# EMG_V02.net
KiCad netlist of a schematic drawn in Altium Designer
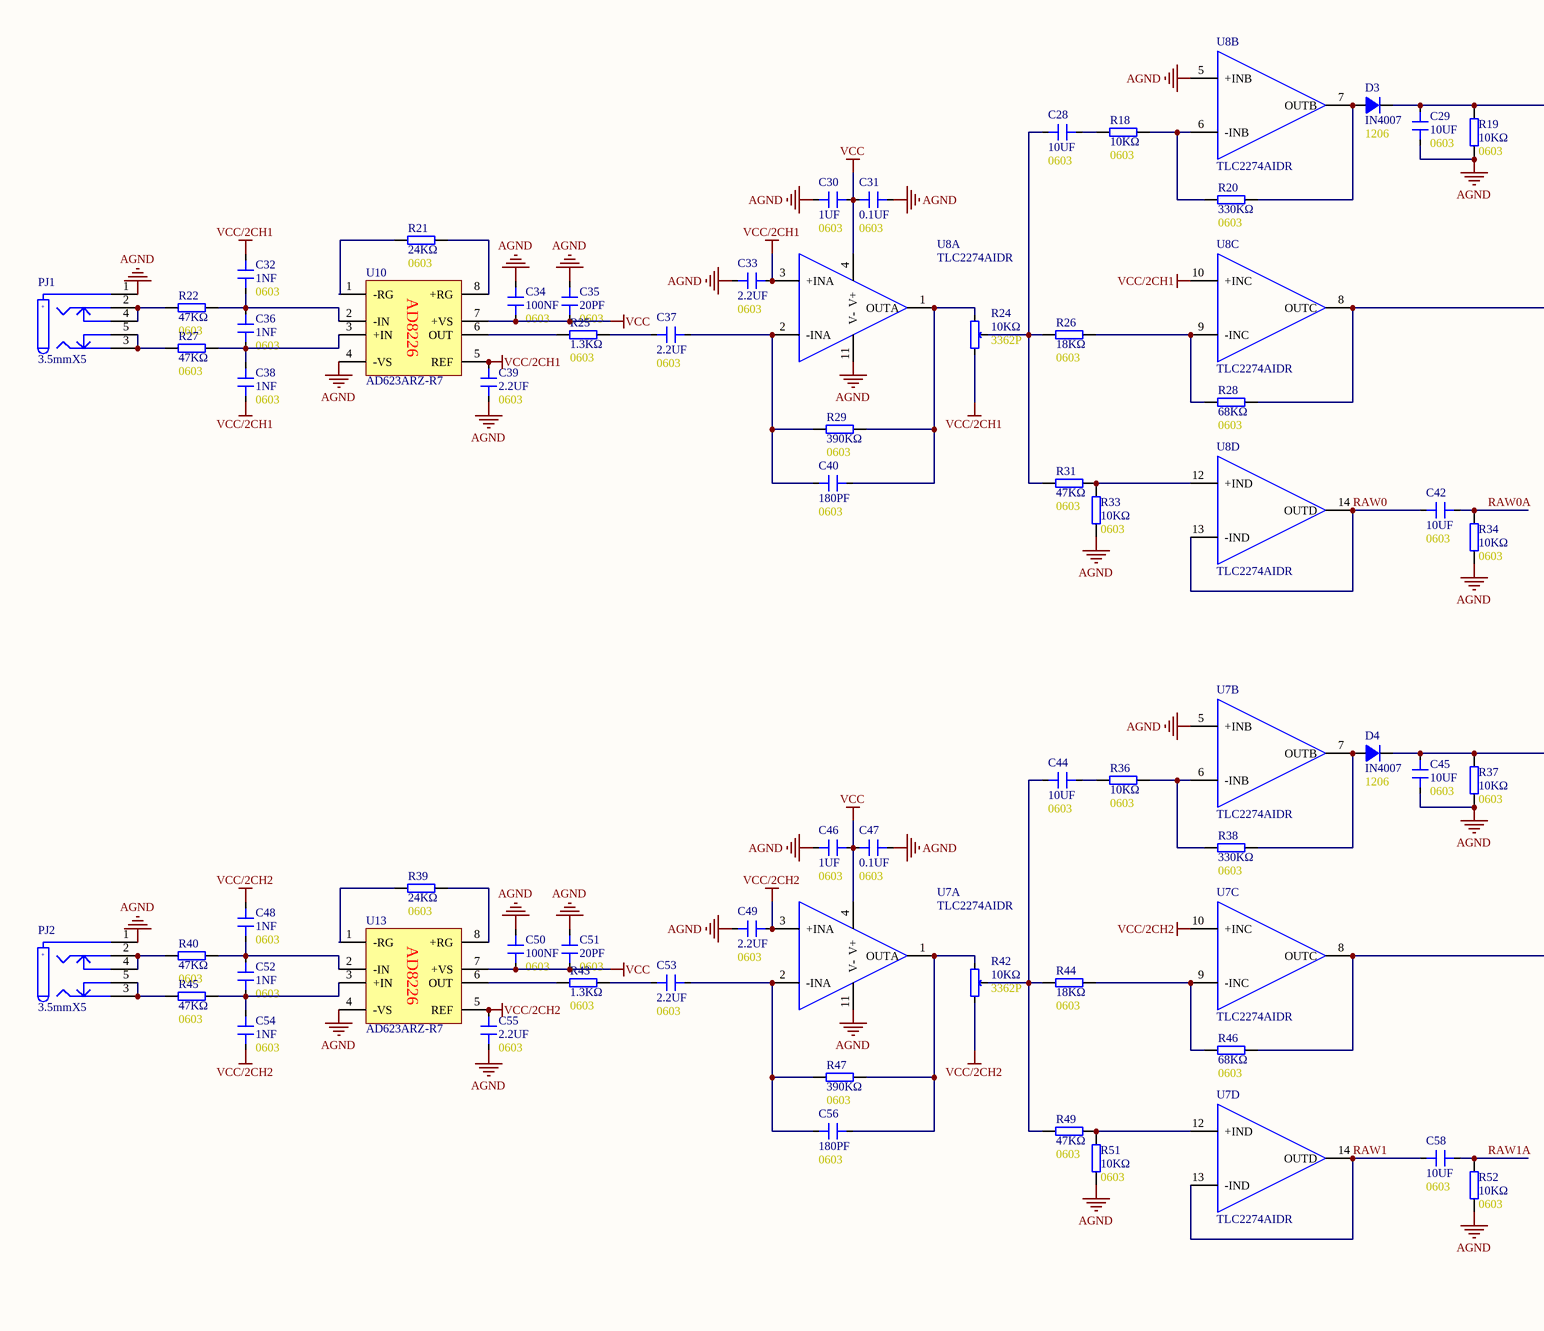
[diagram p0: EMG_V02.SchDoc, top left]
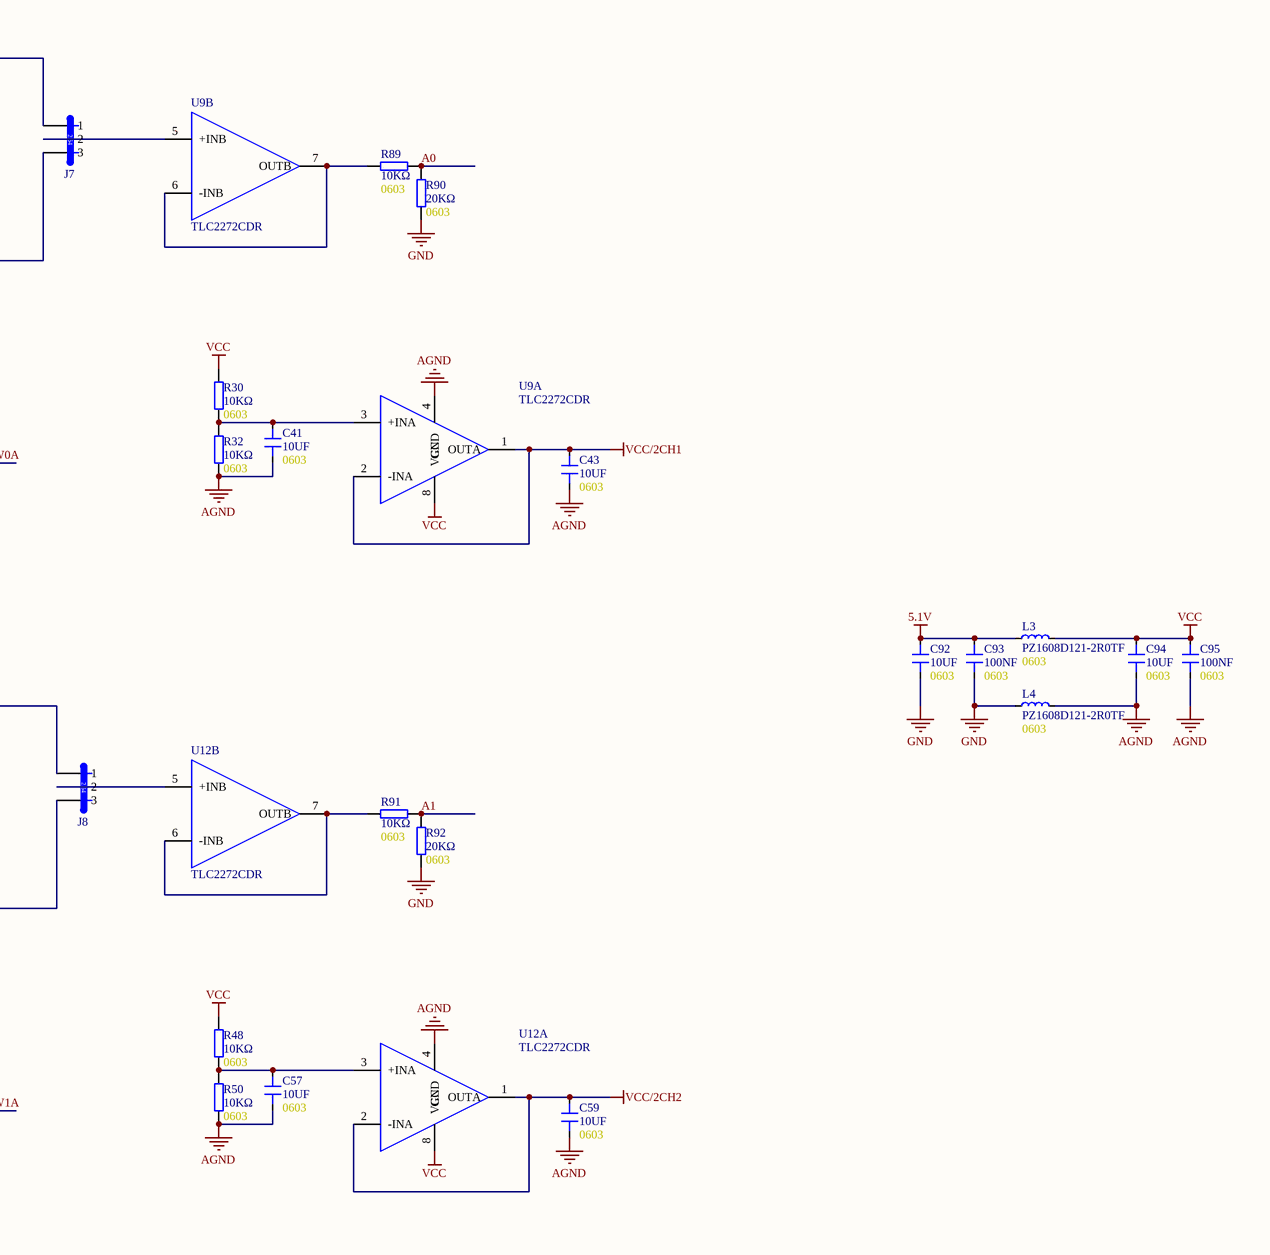
[diagram p1: EMG_V02.SchDoc, top right]
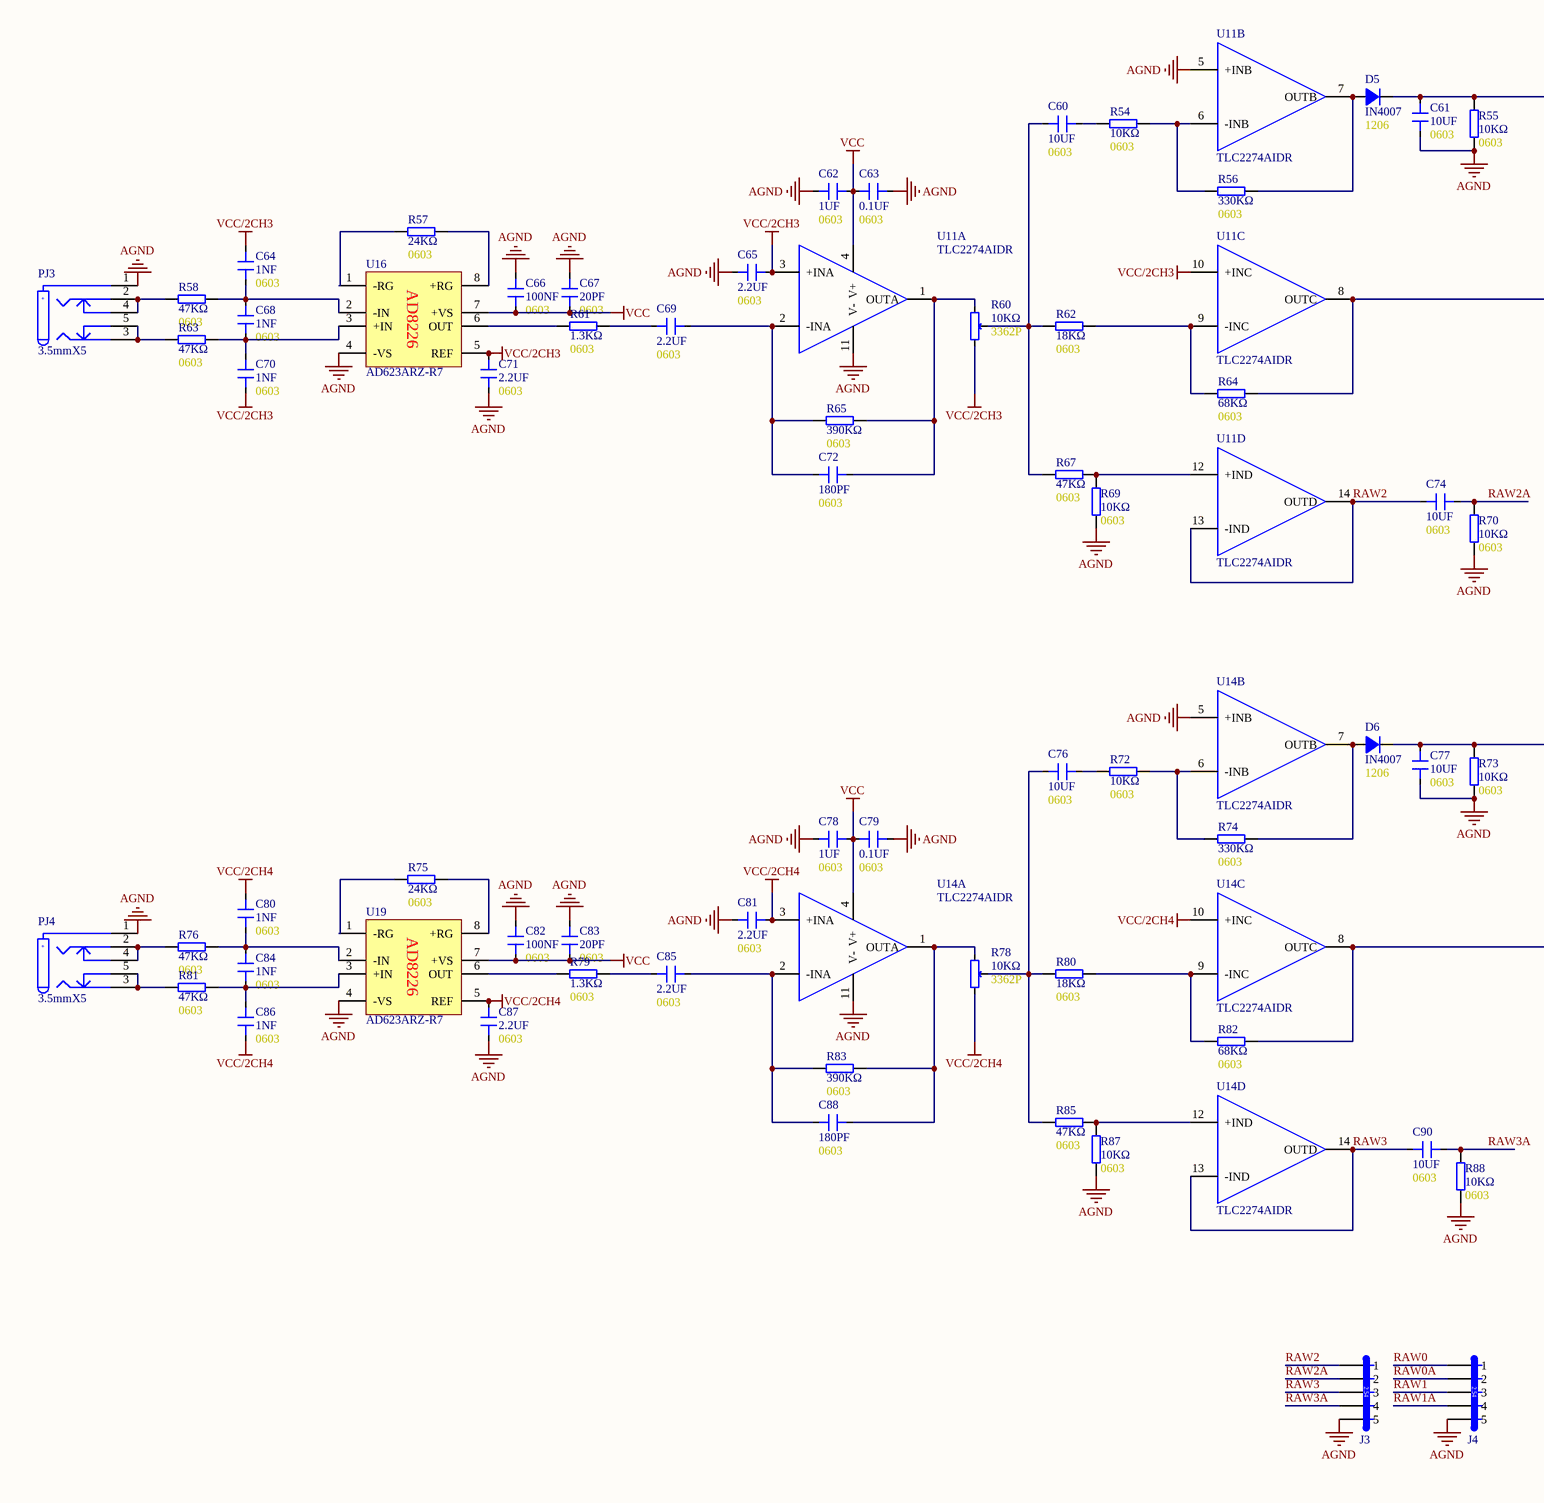
[diagram p2: EMG_V02.SchDoc, bottom left]
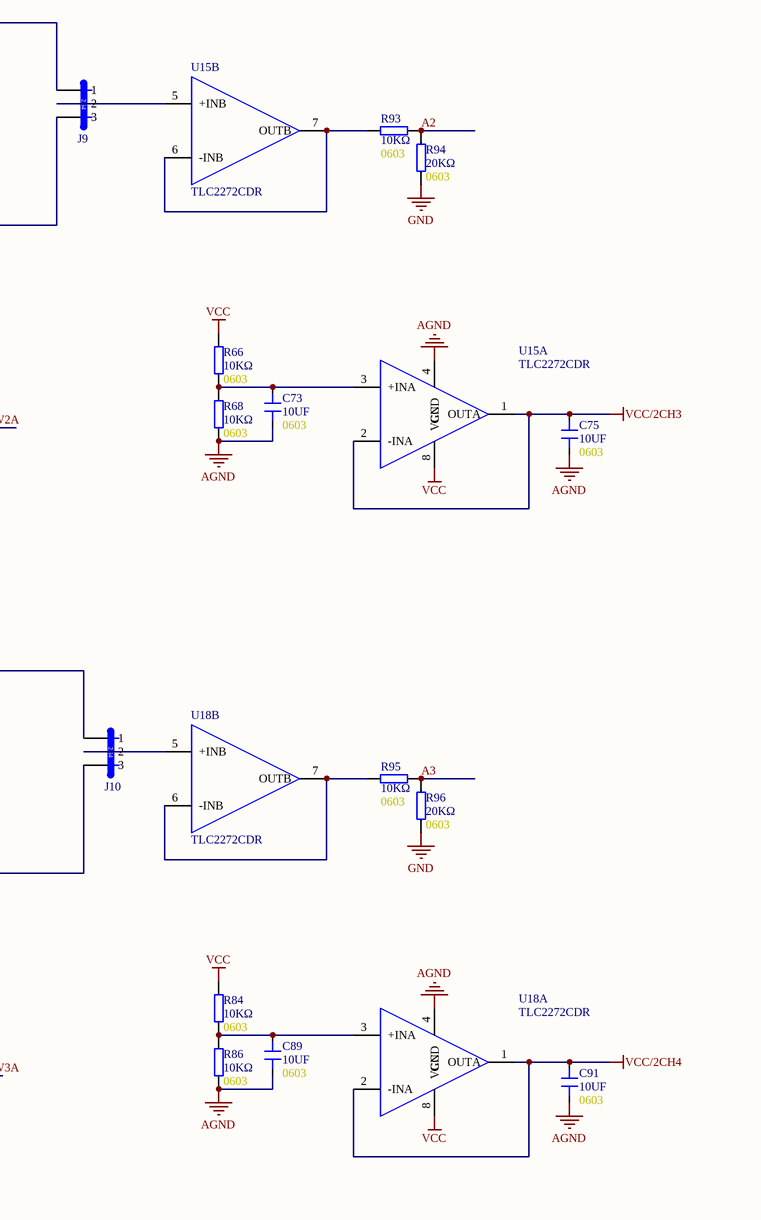
[diagram p3: EMG_V02.SchDoc, bottom right]

(export (version "E")
  (design (tool "Eeschema 10.0.6"))
  (components
    (comp (ref "C28")
      (value "10UF")
      (footprint "CAP - 0603")
      (description "贴片电容，0603封装")
      (fields (field (name "封装类型") "0603"))
      (libsource (lib "冯奇 - 标准集成库") (part "CAP - 0603"))
    )
    (comp (ref "C29")
      (value "10UF")
      (footprint "CAP - 0603")
      (description "贴片电容，0603封装")
      (fields (field (name "封装类型") "0603"))
      (libsource (lib "冯奇 - 标准集成库") (part "CAP - 0603"))
    )
    (comp (ref "C30")
      (value "1UF")
      (footprint "CAP - 0603")
      (description "贴片电容，0603封装")
      (fields (field (name "封装类型") "0603"))
      (libsource (lib "冯奇 - 标准集成库") (part "CAP - 0603"))
    )
    (comp (ref "C31")
      (value "0.1UF")
      (footprint "CAP - 0603")
      (description "贴片电容，0603封装")
      (fields (field (name "封装类型") "0603"))
      (libsource (lib "冯奇 - 标准集成库") (part "CAP - 0603"))
    )
    (comp (ref "C32")
      (value "1NF")
      (footprint "CAP - 0603")
      (description "贴片电容，0603封装")
      (fields (field (name "封装类型") "0603"))
      (libsource (lib "冯奇 - 标准集成库") (part "CAP - 0603"))
    )
    (comp (ref "C33")
      (value "2.2UF")
      (footprint "CAP - 0603")
      (description "贴片电容，0603封装")
      (fields (field (name "封装类型") "0603"))
      (libsource (lib "冯奇 - 标准集成库") (part "CAP - 0603"))
    )
    (comp (ref "C34")
      (value "100NF")
      (footprint "CAP - 0603")
      (description "贴片电容，0603封装")
      (fields (field (name "封装类型") "0603"))
      (libsource (lib "冯奇 - 标准集成库") (part "CAP - 0603"))
    )
    (comp (ref "C35")
      (value "20PF")
      (footprint "CAP - 0603")
      (description "贴片电容，0603封装")
      (fields (field (name "封装类型") "0603"))
      (libsource (lib "冯奇 - 标准集成库") (part "CAP - 0603"))
    )
    (comp (ref "C36")
      (value "1NF")
      (footprint "CAP - 0603")
      (description "贴片电容，0603封装")
      (fields (field (name "封装类型") "0603"))
      (libsource (lib "冯奇 - 标准集成库") (part "CAP - 0603"))
    )
    (comp (ref "C37")
      (value "2.2UF")
      (footprint "CAP - 0603")
      (description "贴片电容，0603封装")
      (fields (field (name "封装类型") "0603"))
      (libsource (lib "冯奇 - 标准集成库") (part "CAP - 0603"))
    )
    (comp (ref "C38")
      (value "1NF")
      (footprint "CAP - 0603")
      (description "贴片电容，0603封装")
      (fields (field (name "封装类型") "0603"))
      (libsource (lib "冯奇 - 标准集成库") (part "CAP - 0603"))
    )
    (comp (ref "C39")
      (value "2.2UF")
      (footprint "CAP - 0603")
      (description "贴片电容，0603封装")
      (fields (field (name "封装类型") "0603"))
      (libsource (lib "冯奇 - 标准集成库") (part "CAP - 0603"))
    )
    (comp (ref "C40")
      (value "180PF")
      (footprint "CAP - 0603")
      (description "贴片电容，0603封装")
      (fields (field (name "封装类型") "0603"))
      (libsource (lib "冯奇 - 标准集成库") (part "CAP - 0603"))
    )
    (comp (ref "C41")
      (value "10UF")
      (footprint "CAP - 0603")
      (description "贴片电容，0603封装")
      (fields (field (name "封装类型") "0603"))
      (libsource (lib "冯奇 - 标准集成库") (part "CAP - 0603"))
    )
    (comp (ref "C42")
      (value "10UF")
      (footprint "CAP - 0603")
      (description "贴片电容，0603封装")
      (fields (field (name "封装类型") "0603"))
      (libsource (lib "冯奇 - 标准集成库") (part "CAP - 0603"))
    )
    (comp (ref "C43")
      (value "10UF")
      (footprint "CAP - 0603")
      (description "贴片电容，0603封装")
      (fields (field (name "封装类型") "0603"))
      (libsource (lib "冯奇 - 标准集成库") (part "CAP - 0603"))
    )
    (comp (ref "C44")
      (value "10UF")
      (footprint "CAP - 0603")
      (description "贴片电容，0603封装")
      (fields (field (name "封装类型") "0603"))
      (libsource (lib "冯奇 - 标准集成库") (part "CAP - 0603"))
    )
    (comp (ref "C45")
      (value "10UF")
      (footprint "CAP - 0603")
      (description "贴片电容，0603封装")
      (fields (field (name "封装类型") "0603"))
      (libsource (lib "冯奇 - 标准集成库") (part "CAP - 0603"))
    )
    (comp (ref "C46")
      (value "1UF")
      (footprint "CAP - 0603")
      (description "贴片电容，0603封装")
      (fields (field (name "封装类型") "0603"))
      (libsource (lib "冯奇 - 标准集成库") (part "CAP - 0603"))
    )
    (comp (ref "C47")
      (value "0.1UF")
      (footprint "CAP - 0603")
      (description "贴片电容，0603封装")
      (fields (field (name "封装类型") "0603"))
      (libsource (lib "冯奇 - 标准集成库") (part "CAP - 0603"))
    )
    (comp (ref "C48")
      (value "1NF")
      (footprint "CAP - 0603")
      (description "贴片电容，0603封装")
      (fields (field (name "封装类型") "0603"))
      (libsource (lib "冯奇 - 标准集成库") (part "CAP - 0603"))
    )
    (comp (ref "C49")
      (value "2.2UF")
      (footprint "CAP - 0603")
      (description "贴片电容，0603封装")
      (fields (field (name "封装类型") "0603"))
      (libsource (lib "冯奇 - 标准集成库") (part "CAP - 0603"))
    )
    (comp (ref "C50")
      (value "100NF")
      (footprint "CAP - 0603")
      (description "贴片电容，0603封装")
      (fields (field (name "封装类型") "0603"))
      (libsource (lib "冯奇 - 标准集成库") (part "CAP - 0603"))
    )
    (comp (ref "C51")
      (value "20PF")
      (footprint "CAP - 0603")
      (description "贴片电容，0603封装")
      (fields (field (name "封装类型") "0603"))
      (libsource (lib "冯奇 - 标准集成库") (part "CAP - 0603"))
    )
    (comp (ref "C52")
      (value "1NF")
      (footprint "CAP - 0603")
      (description "贴片电容，0603封装")
      (fields (field (name "封装类型") "0603"))
      (libsource (lib "冯奇 - 标准集成库") (part "CAP - 0603"))
    )
    (comp (ref "C53")
      (value "2.2UF")
      (footprint "CAP - 0603")
      (description "贴片电容，0603封装")
      (fields (field (name "封装类型") "0603"))
      (libsource (lib "冯奇 - 标准集成库") (part "CAP - 0603"))
    )
    (comp (ref "C54")
      (value "1NF")
      (footprint "CAP - 0603")
      (description "贴片电容，0603封装")
      (fields (field (name "封装类型") "0603"))
      (libsource (lib "冯奇 - 标准集成库") (part "CAP - 0603"))
    )
    (comp (ref "C55")
      (value "2.2UF")
      (footprint "CAP - 0603")
      (description "贴片电容，0603封装")
      (fields (field (name "封装类型") "0603"))
      (libsource (lib "冯奇 - 标准集成库") (part "CAP - 0603"))
    )
    (comp (ref "C56")
      (value "180PF")
      (footprint "CAP - 0603")
      (description "贴片电容，0603封装")
      (fields (field (name "封装类型") "0603"))
      (libsource (lib "冯奇 - 标准集成库") (part "CAP - 0603"))
    )
    (comp (ref "C57")
      (value "10UF")
      (footprint "CAP - 0603")
      (description "贴片电容，0603封装")
      (fields (field (name "封装类型") "0603"))
      (libsource (lib "冯奇 - 标准集成库") (part "CAP - 0603"))
    )
    (comp (ref "C58")
      (value "10UF")
      (footprint "CAP - 0603")
      (description "贴片电容，0603封装")
      (fields (field (name "封装类型") "0603"))
      (libsource (lib "冯奇 - 标准集成库") (part "CAP - 0603"))
    )
    (comp (ref "C59")
      (value "10UF")
      (footprint "CAP - 0603")
      (description "贴片电容，0603封装")
      (fields (field (name "封装类型") "0603"))
      (libsource (lib "冯奇 - 标准集成库") (part "CAP - 0603"))
    )
    (comp (ref "C60")
      (value "10UF")
      (footprint "CAP - 0603")
      (description "贴片电容，0603封装")
      (fields (field (name "封装类型") "0603"))
      (libsource (lib "冯奇 - 标准集成库") (part "CAP - 0603"))
    )
    (comp (ref "C61")
      (value "10UF")
      (footprint "CAP - 0603")
      (description "贴片电容，0603封装")
      (fields (field (name "封装类型") "0603"))
      (libsource (lib "冯奇 - 标准集成库") (part "CAP - 0603"))
    )
    (comp (ref "C62")
      (value "1UF")
      (footprint "CAP - 0603")
      (description "贴片电容，0603封装")
      (fields (field (name "封装类型") "0603"))
      (libsource (lib "冯奇 - 标准集成库") (part "CAP - 0603"))
    )
    (comp (ref "C63")
      (value "0.1UF")
      (footprint "CAP - 0603")
      (description "贴片电容，0603封装")
      (fields (field (name "封装类型") "0603"))
      (libsource (lib "冯奇 - 标准集成库") (part "CAP - 0603"))
    )
    (comp (ref "C64")
      (value "1NF")
      (footprint "CAP - 0603")
      (description "贴片电容，0603封装")
      (fields (field (name "封装类型") "0603"))
      (libsource (lib "冯奇 - 标准集成库") (part "CAP - 0603"))
    )
    (comp (ref "C65")
      (value "2.2UF")
      (footprint "CAP - 0603")
      (description "贴片电容，0603封装")
      (fields (field (name "封装类型") "0603"))
      (libsource (lib "冯奇 - 标准集成库") (part "CAP - 0603"))
    )
    (comp (ref "C66")
      (value "100NF")
      (footprint "CAP - 0603")
      (description "贴片电容，0603封装")
      (fields (field (name "封装类型") "0603"))
      (libsource (lib "冯奇 - 标准集成库") (part "CAP - 0603"))
    )
    (comp (ref "C67")
      (value "20PF")
      (footprint "CAP - 0603")
      (description "贴片电容，0603封装")
      (fields (field (name "封装类型") "0603"))
      (libsource (lib "冯奇 - 标准集成库") (part "CAP - 0603"))
    )
    (comp (ref "C68")
      (value "1NF")
      (footprint "CAP - 0603")
      (description "贴片电容，0603封装")
      (fields (field (name "封装类型") "0603"))
      (libsource (lib "冯奇 - 标准集成库") (part "CAP - 0603"))
    )
    (comp (ref "C69")
      (value "2.2UF")
      (footprint "CAP - 0603")
      (description "贴片电容，0603封装")
      (fields (field (name "封装类型") "0603"))
      (libsource (lib "冯奇 - 标准集成库") (part "CAP - 0603"))
    )
    (comp (ref "C70")
      (value "1NF")
      (footprint "CAP - 0603")
      (description "贴片电容，0603封装")
      (fields (field (name "封装类型") "0603"))
      (libsource (lib "冯奇 - 标准集成库") (part "CAP - 0603"))
    )
    (comp (ref "C71")
      (value "2.2UF")
      (footprint "CAP - 0603")
      (description "贴片电容，0603封装")
      (fields (field (name "封装类型") "0603"))
      (libsource (lib "冯奇 - 标准集成库") (part "CAP - 0603"))
    )
    (comp (ref "C72")
      (value "180PF")
      (footprint "CAP - 0603")
      (description "贴片电容，0603封装")
      (fields (field (name "封装类型") "0603"))
      (libsource (lib "冯奇 - 标准集成库") (part "CAP - 0603"))
    )
    (comp (ref "C73")
      (value "10UF")
      (footprint "CAP - 0603")
      (description "贴片电容，0603封装")
      (fields (field (name "封装类型") "0603"))
      (libsource (lib "冯奇 - 标准集成库") (part "CAP - 0603"))
    )
    (comp (ref "C74")
      (value "10UF")
      (footprint "CAP - 0603")
      (description "贴片电容，0603封装")
      (fields (field (name "封装类型") "0603"))
      (libsource (lib "冯奇 - 标准集成库") (part "CAP - 0603"))
    )
    (comp (ref "C75")
      (value "10UF")
      (footprint "CAP - 0603")
      (description "贴片电容，0603封装")
      (fields (field (name "封装类型") "0603"))
      (libsource (lib "冯奇 - 标准集成库") (part "CAP - 0603"))
    )
    (comp (ref "C76")
      (value "10UF")
      (footprint "CAP - 0603")
      (description "贴片电容，0603封装")
      (fields (field (name "封装类型") "0603"))
      (libsource (lib "冯奇 - 标准集成库") (part "CAP - 0603"))
    )
    (comp (ref "C77")
      (value "10UF")
      (footprint "CAP - 0603")
      (description "贴片电容，0603封装")
      (fields (field (name "封装类型") "0603"))
      (libsource (lib "冯奇 - 标准集成库") (part "CAP - 0603"))
    )
    (comp (ref "C78")
      (value "1UF")
      (footprint "CAP - 0603")
      (description "贴片电容，0603封装")
      (fields (field (name "封装类型") "0603"))
      (libsource (lib "冯奇 - 标准集成库") (part "CAP - 0603"))
    )
    (comp (ref "C79")
      (value "0.1UF")
      (footprint "CAP - 0603")
      (description "贴片电容，0603封装")
      (fields (field (name "封装类型") "0603"))
      (libsource (lib "冯奇 - 标准集成库") (part "CAP - 0603"))
    )
    (comp (ref "C80")
      (value "1NF")
      (footprint "CAP - 0603")
      (description "贴片电容，0603封装")
      (fields (field (name "封装类型") "0603"))
      (libsource (lib "冯奇 - 标准集成库") (part "CAP - 0603"))
    )
    (comp (ref "C81")
      (value "2.2UF")
      (footprint "CAP - 0603")
      (description "贴片电容，0603封装")
      (fields (field (name "封装类型") "0603"))
      (libsource (lib "冯奇 - 标准集成库") (part "CAP - 0603"))
    )
    (comp (ref "C82")
      (value "100NF")
      (footprint "CAP - 0603")
      (description "贴片电容，0603封装")
      (fields (field (name "封装类型") "0603"))
      (libsource (lib "冯奇 - 标准集成库") (part "CAP - 0603"))
    )
    (comp (ref "C83")
      (value "20PF")
      (footprint "CAP - 0603")
      (description "贴片电容，0603封装")
      (fields (field (name "封装类型") "0603"))
      (libsource (lib "冯奇 - 标准集成库") (part "CAP - 0603"))
    )
    (comp (ref "C84")
      (value "1NF")
      (footprint "CAP - 0603")
      (description "贴片电容，0603封装")
      (fields (field (name "封装类型") "0603"))
      (libsource (lib "冯奇 - 标准集成库") (part "CAP - 0603"))
    )
    (comp (ref "C85")
      (value "2.2UF")
      (footprint "CAP - 0603")
      (description "贴片电容，0603封装")
      (fields (field (name "封装类型") "0603"))
      (libsource (lib "冯奇 - 标准集成库") (part "CAP - 0603"))
    )
    (comp (ref "C86")
      (value "1NF")
      (footprint "CAP - 0603")
      (description "贴片电容，0603封装")
      (fields (field (name "封装类型") "0603"))
      (libsource (lib "冯奇 - 标准集成库") (part "CAP - 0603"))
    )
    (comp (ref "C87")
      (value "2.2UF")
      (footprint "CAP - 0603")
      (description "贴片电容，0603封装")
      (fields (field (name "封装类型") "0603"))
      (libsource (lib "冯奇 - 标准集成库") (part "CAP - 0603"))
    )
    (comp (ref "C88")
      (value "180PF")
      (footprint "CAP - 0603")
      (description "贴片电容，0603封装")
      (fields (field (name "封装类型") "0603"))
      (libsource (lib "冯奇 - 标准集成库") (part "CAP - 0603"))
    )
    (comp (ref "C89")
      (value "10UF")
      (footprint "CAP - 0603")
      (description "贴片电容，0603封装")
      (fields (field (name "封装类型") "0603"))
      (libsource (lib "冯奇 - 标准集成库") (part "CAP - 0603"))
    )
    (comp (ref "C90")
      (value "10UF")
      (footprint "CAP - 0603")
      (description "贴片电容，0603封装")
      (fields (field (name "封装类型") "0603"))
      (libsource (lib "冯奇 - 标准集成库") (part "CAP - 0603"))
    )
    (comp (ref "C91")
      (value "10UF")
      (footprint "CAP - 0603")
      (description "贴片电容，0603封装")
      (fields (field (name "封装类型") "0603"))
      (libsource (lib "冯奇 - 标准集成库") (part "CAP - 0603"))
    )
    (comp (ref "C92")
      (value "10UF")
      (footprint "CAP - 0603")
      (description "贴片电容，0603封装")
      (fields (field (name "封装类型") "0603"))
      (libsource (lib "冯奇 - 标准集成库") (part "CAP - 0603"))
    )
    (comp (ref "C93")
      (value "100NF")
      (footprint "CAP - 0603")
      (description "贴片电容，0603封装")
      (fields (field (name "封装类型") "0603"))
      (libsource (lib "冯奇 - 标准集成库") (part "CAP - 0603"))
    )
    (comp (ref "C94")
      (value "10UF")
      (footprint "CAP - 0603")
      (description "贴片电容，0603封装")
      (fields (field (name "封装类型") "0603"))
      (libsource (lib "冯奇 - 标准集成库") (part "CAP - 0603"))
    )
    (comp (ref "C95")
      (value "100NF")
      (footprint "CAP - 0603")
      (description "贴片电容，0603封装")
      (fields (field (name "封装类型") "0603"))
      (libsource (lib "冯奇 - 标准集成库") (part "CAP - 0603"))
    )
    (comp (ref "D3")
      (value "IN4007")
      (footprint "DIO-1206/SOD123")
      (description "二极管，SOD123/1206封装")
      (fields (field (name "封装类型") "1206"))
      (libsource (lib "冯奇 - 标准集成库") (part "DIO/1206"))
    )
    (comp (ref "D4")
      (value "IN4007")
      (footprint "DIO-1206/SOD123")
      (description "二极管，SOD123/1206封装")
      (fields (field (name "封装类型") "1206"))
      (libsource (lib "冯奇 - 标准集成库") (part "DIO/1206"))
    )
    (comp (ref "D5")
      (value "IN4007")
      (footprint "DIO-1206/SOD123")
      (description "二极管，SOD123/1206封装")
      (fields (field (name "封装类型") "1206"))
      (libsource (lib "冯奇 - 标准集成库") (part "DIO/1206"))
    )
    (comp (ref "D6")
      (value "IN4007")
      (footprint "DIO-1206/SOD123")
      (description "二极管，SOD123/1206封装")
      (fields (field (name "封装类型") "1206"))
      (libsource (lib "冯奇 - 标准集成库") (part "DIO/1206"))
    )
    (comp (ref "J3")
      (value "2.54mm")
      (footprint "PIN/2.54 - 05X01")
      (description "普通插针，间距2.54mm，05X01")
      (libsource (lib "冯奇 - 标准集成库") (part "PIN/2.54 - 05X01"))
    )
    (comp (ref "J4")
      (value "2.54mm")
      (footprint "PIN/2.54 - 05X01")
      (description "普通插针，间距2.54mm，05X01")
      (libsource (lib "冯奇 - 标准集成库") (part "PIN/2.54 - 05X01"))
    )
    (comp (ref "J7")
      (value "2.54mm")
      (footprint "PIN/2.54 - 03X01")
      (description "普通插针，间距2.54mm，03X01")
      (libsource (lib "冯奇 - 标准集成库") (part "PIN/2.54 - 03X01"))
    )
    (comp (ref "J8")
      (value "2.54mm")
      (footprint "PIN/2.54 - 03X01")
      (description "普通插针，间距2.54mm，03X01")
      (libsource (lib "冯奇 - 标准集成库") (part "PIN/2.54 - 03X01"))
    )
    (comp (ref "J9")
      (value "2.54mm")
      (footprint "PIN/2.54 - 03X01")
      (description "普通插针，间距2.54mm，03X01")
      (libsource (lib "冯奇 - 标准集成库") (part "PIN/2.54 - 03X01"))
    )
    (comp (ref "J10")
      (value "2.54mm")
      (footprint "PIN/2.54 - 03X01")
      (description "普通插针，间距2.54mm，03X01")
      (libsource (lib "冯奇 - 标准集成库") (part "PIN/2.54 - 03X01"))
    )
    (comp (ref "L3")
      (value "PZ1608D121-2R0TF")
      (footprint "IND/SMD-0603")
      (description "贴片电感，0603封装")
      (fields (field (name "封装类型") "0603"))
      (libsource (lib "冯奇 - 标准集成库") (part "IND/SMD-0603"))
    )
    (comp (ref "L4")
      (value "PZ1608D121-2R0TF")
      (footprint "IND/SMD-0603")
      (description "贴片电感，0603封装")
      (fields (field (name "封装类型") "0603"))
      (libsource (lib "冯奇 - 标准集成库") (part "IND/SMD-0603"))
    )
    (comp (ref "PJ1")
      (value "PJ-3.5")
      (footprint "PJ/3.5MM")
      (description "耳机插座，3.5MM，直插5脚")
      (fields (field (name "封装类型") "3.5mmX5"))
      (libsource (lib "冯奇 - 标准集成库") (part "PJ/3.5MM"))
    )
    (comp (ref "PJ2")
      (value "PJ-3.5")
      (footprint "PJ/3.5MM")
      (description "耳机插座，3.5MM，直插5脚")
      (fields (field (name "封装类型") "3.5mmX5"))
      (libsource (lib "冯奇 - 标准集成库") (part "PJ/3.5MM"))
    )
    (comp (ref "PJ3")
      (value "PJ-3.5")
      (footprint "PJ/3.5MM")
      (description "耳机插座，3.5MM，直插5脚")
      (fields (field (name "封装类型") "3.5mmX5"))
      (libsource (lib "冯奇 - 标准集成库") (part "PJ/3.5MM"))
    )
    (comp (ref "PJ4")
      (value "PJ-3.5")
      (footprint "PJ/3.5MM")
      (description "耳机插座，3.5MM，直插5脚")
      (fields (field (name "封装类型") "3.5mmX5"))
      (libsource (lib "冯奇 - 标准集成库") (part "PJ/3.5MM"))
    )
    (comp (ref "R18")
      (value "10KΩ")
      (footprint "RES/SMD-0603")
      (description "1/10W，50V，贴片电阻，0603封装")
      (fields (field (name "封装类型") "0603"))
      (libsource (lib "冯奇 - 标准集成库") (part "RES/SMD-0603"))
    )
    (comp (ref "R19")
      (value "10KΩ")
      (footprint "RES/SMD-0603")
      (description "1/10W，50V，贴片电阻，0603封装")
      (fields (field (name "封装类型") "0603"))
      (libsource (lib "") (part "RES/SMD-0603_2"))
    )
    (comp (ref "R20")
      (value "330KΩ")
      (footprint "RES/SMD-0603")
      (description "1/10W，50V，贴片电阻，0603封装")
      (fields (field (name "封装类型") "0603"))
      (libsource (lib "冯奇 - 标准集成库") (part "RES/SMD-0603"))
    )
    (comp (ref "R21")
      (value "24KΩ")
      (footprint "RES/SMD-0603")
      (description "1/10W，50V，贴片电阻，0603封装")
      (fields (field (name "封装类型") "0603"))
      (libsource (lib "冯奇 - 标准集成库") (part "RES/SMD-0603"))
    )
    (comp (ref "R22")
      (value "47KΩ")
      (footprint "RES/SMD-0603")
      (description "1/10W，50V，贴片电阻，0603封装")
      (fields (field (name "封装类型") "0603"))
      (libsource (lib "冯奇 - 标准集成库") (part "RES/SMD-0603"))
    )
    (comp (ref "R24")
      (value "10KΩ")
      (footprint "RES/VARI - 3362P")
      (description "可变电阻，3362P型号")
      (fields (field (name "封装类型") "3362P"))
      (libsource (lib "冯奇 - 标准集成库") (part "RES/VARI-3362P"))
    )
    (comp (ref "R25")
      (value "1.3KΩ")
      (footprint "RES/SMD-0603")
      (description "1/10W，50V，贴片电阻，0603封装")
      (fields (field (name "封装类型") "0603"))
      (libsource (lib "冯奇 - 标准集成库") (part "RES/SMD-0603"))
    )
    (comp (ref "R26")
      (value "18KΩ")
      (footprint "RES/SMD-0603")
      (description "1/10W，50V，贴片电阻，0603封装")
      (fields (field (name "封装类型") "0603"))
      (libsource (lib "冯奇 - 标准集成库") (part "RES/SMD-0603"))
    )
    (comp (ref "R27")
      (value "47KΩ")
      (footprint "RES/SMD-0603")
      (description "1/10W，50V，贴片电阻，0603封装")
      (fields (field (name "封装类型") "0603"))
      (libsource (lib "冯奇 - 标准集成库") (part "RES/SMD-0603"))
    )
    (comp (ref "R28")
      (value "68KΩ")
      (footprint "RES/SMD-0603")
      (description "1/10W，50V，贴片电阻，0603封装")
      (fields (field (name "封装类型") "0603"))
      (libsource (lib "冯奇 - 标准集成库") (part "RES/SMD-0603"))
    )
    (comp (ref "R29")
      (value "390KΩ")
      (footprint "RES/SMD-0603")
      (description "1/10W，50V，贴片电阻，0603封装")
      (fields (field (name "封装类型") "0603"))
      (libsource (lib "冯奇 - 标准集成库") (part "RES/SMD-0603"))
    )
    (comp (ref "R30")
      (value "10KΩ")
      (footprint "RES/SMD-0603")
      (description "1/10W，50V，贴片电阻，0603封装")
      (fields (field (name "封装类型") "0603"))
      (libsource (lib "") (part "RES/SMD-0603_1"))
    )
    (comp (ref "R31")
      (value "47KΩ")
      (footprint "RES/SMD-0603")
      (description "1/10W，50V，贴片电阻，0603封装")
      (fields (field (name "封装类型") "0603"))
      (libsource (lib "冯奇 - 标准集成库") (part "RES/SMD-0603"))
    )
    (comp (ref "R32")
      (value "10KΩ")
      (footprint "RES/SMD-0603")
      (description "1/10W，50V，贴片电阻，0603封装")
      (fields (field (name "封装类型") "0603"))
      (libsource (lib "") (part "RES/SMD-0603_1"))
    )
    (comp (ref "R33")
      (value "10KΩ")
      (footprint "RES/SMD-0603")
      (description "1/10W，50V，贴片电阻，0603封装")
      (fields (field (name "封装类型") "0603"))
      (libsource (lib "") (part "RES/SMD-0603_2"))
    )
    (comp (ref "R34")
      (value "10KΩ")
      (footprint "RES/SMD-0603")
      (description "1/10W，50V，贴片电阻，0603封装")
      (fields (field (name "封装类型") "0603"))
      (libsource (lib "") (part "RES/SMD-0603_2"))
    )
    (comp (ref "R36")
      (value "10KΩ")
      (footprint "RES/SMD-0603")
      (description "1/10W，50V，贴片电阻，0603封装")
      (fields (field (name "封装类型") "0603"))
      (libsource (lib "冯奇 - 标准集成库") (part "RES/SMD-0603"))
    )
    (comp (ref "R37")
      (value "10KΩ")
      (footprint "RES/SMD-0603")
      (description "1/10W，50V，贴片电阻，0603封装")
      (fields (field (name "封装类型") "0603"))
      (libsource (lib "") (part "RES/SMD-0603_2"))
    )
    (comp (ref "R38")
      (value "330KΩ")
      (footprint "RES/SMD-0603")
      (description "1/10W，50V，贴片电阻，0603封装")
      (fields (field (name "封装类型") "0603"))
      (libsource (lib "冯奇 - 标准集成库") (part "RES/SMD-0603"))
    )
    (comp (ref "R39")
      (value "24KΩ")
      (footprint "RES/SMD-0603")
      (description "1/10W，50V，贴片电阻，0603封装")
      (fields (field (name "封装类型") "0603"))
      (libsource (lib "冯奇 - 标准集成库") (part "RES/SMD-0603"))
    )
    (comp (ref "R40")
      (value "47KΩ")
      (footprint "RES/SMD-0603")
      (description "1/10W，50V，贴片电阻，0603封装")
      (fields (field (name "封装类型") "0603"))
      (libsource (lib "冯奇 - 标准集成库") (part "RES/SMD-0603"))
    )
    (comp (ref "R42")
      (value "10KΩ")
      (footprint "RES/VARI - 3362P")
      (description "可变电阻，3362P型号")
      (fields (field (name "封装类型") "3362P"))
      (libsource (lib "冯奇 - 标准集成库") (part "RES/VARI-3362P"))
    )
    (comp (ref "R43")
      (value "1.3KΩ")
      (footprint "RES/SMD-0603")
      (description "1/10W，50V，贴片电阻，0603封装")
      (fields (field (name "封装类型") "0603"))
      (libsource (lib "冯奇 - 标准集成库") (part "RES/SMD-0603"))
    )
    (comp (ref "R44")
      (value "18KΩ")
      (footprint "RES/SMD-0603")
      (description "1/10W，50V，贴片电阻，0603封装")
      (fields (field (name "封装类型") "0603"))
      (libsource (lib "冯奇 - 标准集成库") (part "RES/SMD-0603"))
    )
    (comp (ref "R45")
      (value "47KΩ")
      (footprint "RES/SMD-0603")
      (description "1/10W，50V，贴片电阻，0603封装")
      (fields (field (name "封装类型") "0603"))
      (libsource (lib "冯奇 - 标准集成库") (part "RES/SMD-0603"))
    )
    (comp (ref "R46")
      (value "68KΩ")
      (footprint "RES/SMD-0603")
      (description "1/10W，50V，贴片电阻，0603封装")
      (fields (field (name "封装类型") "0603"))
      (libsource (lib "冯奇 - 标准集成库") (part "RES/SMD-0603"))
    )
    (comp (ref "R47")
      (value "390KΩ")
      (footprint "RES/SMD-0603")
      (description "1/10W，50V，贴片电阻，0603封装")
      (fields (field (name "封装类型") "0603"))
      (libsource (lib "冯奇 - 标准集成库") (part "RES/SMD-0603"))
    )
    (comp (ref "R48")
      (value "10KΩ")
      (footprint "RES/SMD-0603")
      (description "1/10W，50V，贴片电阻，0603封装")
      (fields (field (name "封装类型") "0603"))
      (libsource (lib "") (part "RES/SMD-0603_1"))
    )
    (comp (ref "R49")
      (value "47KΩ")
      (footprint "RES/SMD-0603")
      (description "1/10W，50V，贴片电阻，0603封装")
      (fields (field (name "封装类型") "0603"))
      (libsource (lib "冯奇 - 标准集成库") (part "RES/SMD-0603"))
    )
    (comp (ref "R50")
      (value "10KΩ")
      (footprint "RES/SMD-0603")
      (description "1/10W，50V，贴片电阻，0603封装")
      (fields (field (name "封装类型") "0603"))
      (libsource (lib "") (part "RES/SMD-0603_1"))
    )
    (comp (ref "R51")
      (value "10KΩ")
      (footprint "RES/SMD-0603")
      (description "1/10W，50V，贴片电阻，0603封装")
      (fields (field (name "封装类型") "0603"))
      (libsource (lib "") (part "RES/SMD-0603_2"))
    )
    (comp (ref "R52")
      (value "10KΩ")
      (footprint "RES/SMD-0603")
      (description "1/10W，50V，贴片电阻，0603封装")
      (fields (field (name "封装类型") "0603"))
      (libsource (lib "") (part "RES/SMD-0603_2"))
    )
    (comp (ref "R54")
      (value "10KΩ")
      (footprint "RES/SMD-0603")
      (description "1/10W，50V，贴片电阻，0603封装")
      (fields (field (name "封装类型") "0603"))
      (libsource (lib "冯奇 - 标准集成库") (part "RES/SMD-0603"))
    )
    (comp (ref "R55")
      (value "10KΩ")
      (footprint "RES/SMD-0603")
      (description "1/10W，50V，贴片电阻，0603封装")
      (fields (field (name "封装类型") "0603"))
      (libsource (lib "") (part "RES/SMD-0603_2"))
    )
    (comp (ref "R56")
      (value "330KΩ")
      (footprint "RES/SMD-0603")
      (description "1/10W，50V，贴片电阻，0603封装")
      (fields (field (name "封装类型") "0603"))
      (libsource (lib "冯奇 - 标准集成库") (part "RES/SMD-0603"))
    )
    (comp (ref "R57")
      (value "24KΩ")
      (footprint "RES/SMD-0603")
      (description "1/10W，50V，贴片电阻，0603封装")
      (fields (field (name "封装类型") "0603"))
      (libsource (lib "冯奇 - 标准集成库") (part "RES/SMD-0603"))
    )
    (comp (ref "R58")
      (value "47KΩ")
      (footprint "RES/SMD-0603")
      (description "1/10W，50V，贴片电阻，0603封装")
      (fields (field (name "封装类型") "0603"))
      (libsource (lib "冯奇 - 标准集成库") (part "RES/SMD-0603"))
    )
    (comp (ref "R60")
      (value "10KΩ")
      (footprint "RES/VARI - 3362P")
      (description "可变电阻，3362P型号")
      (fields (field (name "封装类型") "3362P"))
      (libsource (lib "冯奇 - 标准集成库") (part "RES/VARI-3362P"))
    )
    (comp (ref "R61")
      (value "1.3KΩ")
      (footprint "RES/SMD-0603")
      (description "1/10W，50V，贴片电阻，0603封装")
      (fields (field (name "封装类型") "0603"))
      (libsource (lib "冯奇 - 标准集成库") (part "RES/SMD-0603"))
    )
    (comp (ref "R62")
      (value "18KΩ")
      (footprint "RES/SMD-0603")
      (description "1/10W，50V，贴片电阻，0603封装")
      (fields (field (name "封装类型") "0603"))
      (libsource (lib "冯奇 - 标准集成库") (part "RES/SMD-0603"))
    )
    (comp (ref "R63")
      (value "47KΩ")
      (footprint "RES/SMD-0603")
      (description "1/10W，50V，贴片电阻，0603封装")
      (fields (field (name "封装类型") "0603"))
      (libsource (lib "冯奇 - 标准集成库") (part "RES/SMD-0603"))
    )
    (comp (ref "R64")
      (value "68KΩ")
      (footprint "RES/SMD-0603")
      (description "1/10W，50V，贴片电阻，0603封装")
      (fields (field (name "封装类型") "0603"))
      (libsource (lib "冯奇 - 标准集成库") (part "RES/SMD-0603"))
    )
    (comp (ref "R65")
      (value "390KΩ")
      (footprint "RES/SMD-0603")
      (description "1/10W，50V，贴片电阻，0603封装")
      (fields (field (name "封装类型") "0603"))
      (libsource (lib "冯奇 - 标准集成库") (part "RES/SMD-0603"))
    )
    (comp (ref "R66")
      (value "10KΩ")
      (footprint "RES/SMD-0603")
      (description "1/10W，50V，贴片电阻，0603封装")
      (fields (field (name "封装类型") "0603"))
      (libsource (lib "") (part "RES/SMD-0603_1"))
    )
    (comp (ref "R67")
      (value "47KΩ")
      (footprint "RES/SMD-0603")
      (description "1/10W，50V，贴片电阻，0603封装")
      (fields (field (name "封装类型") "0603"))
      (libsource (lib "冯奇 - 标准集成库") (part "RES/SMD-0603"))
    )
    (comp (ref "R68")
      (value "10KΩ")
      (footprint "RES/SMD-0603")
      (description "1/10W，50V，贴片电阻，0603封装")
      (fields (field (name "封装类型") "0603"))
      (libsource (lib "") (part "RES/SMD-0603_1"))
    )
    (comp (ref "R69")
      (value "10KΩ")
      (footprint "RES/SMD-0603")
      (description "1/10W，50V，贴片电阻，0603封装")
      (fields (field (name "封装类型") "0603"))
      (libsource (lib "") (part "RES/SMD-0603_2"))
    )
    (comp (ref "R70")
      (value "10KΩ")
      (footprint "RES/SMD-0603")
      (description "1/10W，50V，贴片电阻，0603封装")
      (fields (field (name "封装类型") "0603"))
      (libsource (lib "") (part "RES/SMD-0603_2"))
    )
    (comp (ref "R72")
      (value "10KΩ")
      (footprint "RES/SMD-0603")
      (description "1/10W，50V，贴片电阻，0603封装")
      (fields (field (name "封装类型") "0603"))
      (libsource (lib "冯奇 - 标准集成库") (part "RES/SMD-0603"))
    )
    (comp (ref "R73")
      (value "10KΩ")
      (footprint "RES/SMD-0603")
      (description "1/10W，50V，贴片电阻，0603封装")
      (fields (field (name "封装类型") "0603"))
      (libsource (lib "") (part "RES/SMD-0603_2"))
    )
    (comp (ref "R74")
      (value "330KΩ")
      (footprint "RES/SMD-0603")
      (description "1/10W，50V，贴片电阻，0603封装")
      (fields (field (name "封装类型") "0603"))
      (libsource (lib "冯奇 - 标准集成库") (part "RES/SMD-0603"))
    )
    (comp (ref "R75")
      (value "24KΩ")
      (footprint "RES/SMD-0603")
      (description "1/10W，50V，贴片电阻，0603封装")
      (fields (field (name "封装类型") "0603"))
      (libsource (lib "冯奇 - 标准集成库") (part "RES/SMD-0603"))
    )
    (comp (ref "R76")
      (value "47KΩ")
      (footprint "RES/SMD-0603")
      (description "1/10W，50V，贴片电阻，0603封装")
      (fields (field (name "封装类型") "0603"))
      (libsource (lib "冯奇 - 标准集成库") (part "RES/SMD-0603"))
    )
    (comp (ref "R78")
      (value "10KΩ")
      (footprint "RES/VARI - 3362P")
      (description "可变电阻，3362P型号")
      (fields (field (name "封装类型") "3362P"))
      (libsource (lib "冯奇 - 标准集成库") (part "RES/VARI-3362P"))
    )
    (comp (ref "R79")
      (value "1.3KΩ")
      (footprint "RES/SMD-0603")
      (description "1/10W，50V，贴片电阻，0603封装")
      (fields (field (name "封装类型") "0603"))
      (libsource (lib "冯奇 - 标准集成库") (part "RES/SMD-0603"))
    )
    (comp (ref "R80")
      (value "18KΩ")
      (footprint "RES/SMD-0603")
      (description "1/10W，50V，贴片电阻，0603封装")
      (fields (field (name "封装类型") "0603"))
      (libsource (lib "冯奇 - 标准集成库") (part "RES/SMD-0603"))
    )
    (comp (ref "R81")
      (value "47KΩ")
      (footprint "RES/SMD-0603")
      (description "1/10W，50V，贴片电阻，0603封装")
      (fields (field (name "封装类型") "0603"))
      (libsource (lib "冯奇 - 标准集成库") (part "RES/SMD-0603"))
    )
    (comp (ref "R82")
      (value "68KΩ")
      (footprint "RES/SMD-0603")
      (description "1/10W，50V，贴片电阻，0603封装")
      (fields (field (name "封装类型") "0603"))
      (libsource (lib "冯奇 - 标准集成库") (part "RES/SMD-0603"))
    )
    (comp (ref "R83")
      (value "390KΩ")
      (footprint "RES/SMD-0603")
      (description "1/10W，50V，贴片电阻，0603封装")
      (fields (field (name "封装类型") "0603"))
      (libsource (lib "冯奇 - 标准集成库") (part "RES/SMD-0603"))
    )
    (comp (ref "R84")
      (value "10KΩ")
      (footprint "RES/SMD-0603")
      (description "1/10W，50V，贴片电阻，0603封装")
      (fields (field (name "封装类型") "0603"))
      (libsource (lib "") (part "RES/SMD-0603_1"))
    )
    (comp (ref "R85")
      (value "47KΩ")
      (footprint "RES/SMD-0603")
      (description "1/10W，50V，贴片电阻，0603封装")
      (fields (field (name "封装类型") "0603"))
      (libsource (lib "冯奇 - 标准集成库") (part "RES/SMD-0603"))
    )
    (comp (ref "R86")
      (value "10KΩ")
      (footprint "RES/SMD-0603")
      (description "1/10W，50V，贴片电阻，0603封装")
      (fields (field (name "封装类型") "0603"))
      (libsource (lib "") (part "RES/SMD-0603_1"))
    )
    (comp (ref "R87")
      (value "10KΩ")
      (footprint "RES/SMD-0603")
      (description "1/10W，50V，贴片电阻，0603封装")
      (fields (field (name "封装类型") "0603"))
      (libsource (lib "") (part "RES/SMD-0603_2"))
    )
    (comp (ref "R88")
      (value "10KΩ")
      (footprint "RES/SMD-0603")
      (description "1/10W，50V，贴片电阻，0603封装")
      (fields (field (name "封装类型") "0603"))
      (libsource (lib "") (part "RES/SMD-0603_2"))
    )
    (comp (ref "R89")
      (value "10KΩ")
      (footprint "RES/SMD-0603")
      (description "1/10W，50V，贴片电阻，0603封装")
      (fields (field (name "封装类型") "0603"))
      (libsource (lib "冯奇 - 标准集成库") (part "RES/SMD-0603"))
    )
    (comp (ref "R90")
      (value "20KΩ")
      (footprint "RES/SMD-0603")
      (description "1/10W，50V，贴片电阻，0603封装")
      (fields (field (name "封装类型") "0603"))
      (libsource (lib "") (part "RES/SMD-0603_2"))
    )
    (comp (ref "R91")
      (value "10KΩ")
      (footprint "RES/SMD-0603")
      (description "1/10W，50V，贴片电阻，0603封装")
      (fields (field (name "封装类型") "0603"))
      (libsource (lib "冯奇 - 标准集成库") (part "RES/SMD-0603"))
    )
    (comp (ref "R92")
      (value "20KΩ")
      (footprint "RES/SMD-0603")
      (description "1/10W，50V，贴片电阻，0603封装")
      (fields (field (name "封装类型") "0603"))
      (libsource (lib "") (part "RES/SMD-0603_2"))
    )
    (comp (ref "R93")
      (value "10KΩ")
      (footprint "RES/SMD-0603")
      (description "1/10W，50V，贴片电阻，0603封装")
      (fields (field (name "封装类型") "0603"))
      (libsource (lib "冯奇 - 标准集成库") (part "RES/SMD-0603"))
    )
    (comp (ref "R94")
      (value "20KΩ")
      (footprint "RES/SMD-0603")
      (description "1/10W，50V，贴片电阻，0603封装")
      (fields (field (name "封装类型") "0603"))
      (libsource (lib "") (part "RES/SMD-0603_2"))
    )
    (comp (ref "R95")
      (value "10KΩ")
      (footprint "RES/SMD-0603")
      (description "1/10W，50V，贴片电阻，0603封装")
      (fields (field (name "封装类型") "0603"))
      (libsource (lib "冯奇 - 标准集成库") (part "RES/SMD-0603"))
    )
    (comp (ref "R96")
      (value "20KΩ")
      (footprint "RES/SMD-0603")
      (description "1/10W，50V，贴片电阻，0603封装")
      (fields (field (name "封装类型") "0603"))
      (libsource (lib "") (part "RES/SMD-0603_2"))
    )
    (comp (ref "U7")
      (value "TLC2274AIDR")
      (footprint "SOP-14/150MIL")
      (description "精密运算放大器")
      (libsource (lib "冯奇 - 标准集成库") (part "TLC2274AIDR"))
    )
    (comp (ref "U8")
      (value "TLC2274AIDR")
      (footprint "SOP-14/150MIL")
      (description "精密运算放大器")
      (libsource (lib "冯奇 - 标准集成库") (part "TLC2274AIDR"))
    )
    (comp (ref "U9")
      (value "TLC2272CDR")
      (footprint "SOP-08/150MIL")
      (description "精密运算放大器，双通道")
      (libsource (lib "冯奇 - 标准集成库") (part "TLC2272CDR"))
    )
    (comp (ref "U10")
      (value "AD623ARZ-R7")
      (footprint "SOP-08/150MIL")
      (description "仪表放大器")
      (libsource (lib "冯奇 - 标准集成库") (part "AD623ARZ-R7"))
    )
    (comp (ref "U11")
      (value "TLC2274AIDR")
      (footprint "SOP-14/150MIL")
      (description "精密运算放大器")
      (libsource (lib "冯奇 - 标准集成库") (part "TLC2274AIDR"))
    )
    (comp (ref "U12")
      (value "TLC2272CDR")
      (footprint "SOP-08/150MIL")
      (description "精密运算放大器，双通道")
      (libsource (lib "冯奇 - 标准集成库") (part "TLC2272CDR"))
    )
    (comp (ref "U13")
      (value "AD623ARZ-R7")
      (footprint "SOP-08/150MIL")
      (description "仪表放大器")
      (libsource (lib "冯奇 - 标准集成库") (part "AD623ARZ-R7"))
    )
    (comp (ref "U14")
      (value "TLC2274AIDR")
      (footprint "SOP-14/150MIL")
      (description "精密运算放大器")
      (libsource (lib "冯奇 - 标准集成库") (part "TLC2274AIDR"))
    )
    (comp (ref "U15")
      (value "TLC2272CDR")
      (footprint "SOP-08/150MIL")
      (description "精密运算放大器，双通道")
      (libsource (lib "冯奇 - 标准集成库") (part "TLC2272CDR"))
    )
    (comp (ref "U16")
      (value "AD623ARZ-R7")
      (footprint "SOP-08/150MIL")
      (description "仪表放大器")
      (libsource (lib "冯奇 - 标准集成库") (part "AD623ARZ-R7"))
    )
    (comp (ref "U18")
      (value "TLC2272CDR")
      (footprint "SOP-08/150MIL")
      (description "精密运算放大器，双通道")
      (libsource (lib "冯奇 - 标准集成库") (part "TLC2272CDR"))
    )
    (comp (ref "U19")
      (value "AD623ARZ-R7")
      (footprint "SOP-08/150MIL")
      (description "仪表放大器")
      (libsource (lib "冯奇 - 标准集成库") (part "AD623ARZ-R7"))
    )
  )
  (nets
    (net (code "1") (name "/A0") (class "Default")
      (node (ref "R89") (pin "2") (pinfunction "2_2") (pintype "passive"))
      (node (ref "R90") (pin "2") (pinfunction "2_2") (pintype "passive"))
    )
    (net (code "2") (name "/A1") (class "Default")
      (node (ref "R91") (pin "2") (pinfunction "2_2") (pintype "passive"))
      (node (ref "R92") (pin "2") (pinfunction "2_2") (pintype "passive"))
    )
    (net (code "3") (name "/A2") (class "Default")
      (node (ref "R93") (pin "2") (pinfunction "2_2") (pintype "passive"))
      (node (ref "R94") (pin "2") (pinfunction "2_2") (pintype "passive"))
    )
    (net (code "4") (name "/A3") (class "Default")
      (node (ref "R95") (pin "2") (pinfunction "2_2") (pintype "passive"))
      (node (ref "R96") (pin "2") (pinfunction "2_2") (pintype "passive"))
    )
    (net (code "5") (name "/RAW0") (class "Default")
      (node (ref "C42") (pin "2") (pinfunction "2_2") (pintype "passive"))
      (node (ref "J4") (pin "1") (pinfunction "1_1") (pintype "passive"))
      (node (ref "U8") (pin "13") (pinfunction "-IND_13") (pintype "passive"))
      (node (ref "U8") (pin "14") (pinfunction "OUTD_14") (pintype "passive"))
    )
    (net (code "6") (name "/RAW0A") (class "Default")
      (node (ref "C42") (pin "1") (pinfunction "1_1") (pintype "passive"))
      (node (ref "J4") (pin "2") (pinfunction "2_2") (pintype "passive"))
      (node (ref "R34") (pin "2") (pinfunction "2_2") (pintype "passive"))
    )
    (net (code "7") (name "/RAW1") (class "Default")
      (node (ref "C58") (pin "2") (pinfunction "2_2") (pintype "passive"))
      (node (ref "J4") (pin "3") (pinfunction "3_3") (pintype "passive"))
      (node (ref "U7") (pin "13") (pinfunction "-IND_13") (pintype "passive"))
      (node (ref "U7") (pin "14") (pinfunction "OUTD_14") (pintype "passive"))
    )
    (net (code "8") (name "/RAW1A") (class "Default")
      (node (ref "C58") (pin "1") (pinfunction "1_1") (pintype "passive"))
      (node (ref "J4") (pin "4") (pinfunction "4_4") (pintype "passive"))
      (node (ref "R52") (pin "2") (pinfunction "2_2") (pintype "passive"))
    )
    (net (code "9") (name "/RAW2") (class "Default")
      (node (ref "C74") (pin "2") (pinfunction "2_2") (pintype "passive"))
      (node (ref "J3") (pin "1") (pinfunction "1_1") (pintype "passive"))
      (node (ref "U11") (pin "13") (pinfunction "-IND_13") (pintype "passive"))
      (node (ref "U11") (pin "14") (pinfunction "OUTD_14") (pintype "passive"))
    )
    (net (code "10") (name "/RAW2A") (class "Default")
      (node (ref "C74") (pin "1") (pinfunction "1_1") (pintype "passive"))
      (node (ref "J3") (pin "2") (pinfunction "2_2") (pintype "passive"))
      (node (ref "R70") (pin "2") (pinfunction "2_2") (pintype "passive"))
    )
    (net (code "11") (name "/RAW3") (class "Default")
      (node (ref "C90") (pin "2") (pinfunction "2_2") (pintype "passive"))
      (node (ref "J3") (pin "3") (pinfunction "3_3") (pintype "passive"))
      (node (ref "U14") (pin "13") (pinfunction "-IND_13") (pintype "passive"))
      (node (ref "U14") (pin "14") (pinfunction "OUTD_14") (pintype "passive"))
    )
    (net (code "12") (name "/RAW3A") (class "Default")
      (node (ref "C90") (pin "1") (pinfunction "1_1") (pintype "passive"))
      (node (ref "J3") (pin "4") (pinfunction "4_4") (pintype "passive"))
      (node (ref "R88") (pin "2") (pinfunction "2_2") (pintype "passive"))
    )
    (net (code "13") (name "5.1V") (class "Default")
      (node (ref "C92") (pin "2") (pinfunction "2_2") (pintype "passive"))
      (node (ref "C93") (pin "2") (pinfunction "2_2") (pintype "passive"))
      (node (ref "L3") (pin "1") (pinfunction "1_1") (pintype "passive"))
    )
    (net (code "14") (name "AGND") (class "Default")
      (node (ref "C29") (pin "2") (pinfunction "2_2") (pintype "passive"))
      (node (ref "C30") (pin "2") (pinfunction "2_2") (pintype "passive"))
      (node (ref "C31") (pin "1") (pinfunction "1_1") (pintype "passive"))
      (node (ref "C33") (pin "2") (pinfunction "2_2") (pintype "passive"))
      (node (ref "C34") (pin "2") (pinfunction "2_2") (pintype "passive"))
      (node (ref "C35") (pin "2") (pinfunction "2_2") (pintype "passive"))
      (node (ref "C39") (pin "1") (pinfunction "1_1") (pintype "passive"))
      (node (ref "C41") (pin "2") (pinfunction "2_2") (pintype "passive"))
      (node (ref "C43") (pin "2") (pinfunction "2_2") (pintype "passive"))
      (node (ref "C45") (pin "2") (pinfunction "2_2") (pintype "passive"))
      (node (ref "C46") (pin "2") (pinfunction "2_2") (pintype "passive"))
      (node (ref "C47") (pin "1") (pinfunction "1_1") (pintype "passive"))
      (node (ref "C49") (pin "2") (pinfunction "2_2") (pintype "passive"))
      (node (ref "C50") (pin "2") (pinfunction "2_2") (pintype "passive"))
      (node (ref "C51") (pin "2") (pinfunction "2_2") (pintype "passive"))
      (node (ref "C55") (pin "1") (pinfunction "1_1") (pintype "passive"))
      (node (ref "C57") (pin "2") (pinfunction "2_2") (pintype "passive"))
      (node (ref "C59") (pin "2") (pinfunction "2_2") (pintype "passive"))
      (node (ref "C61") (pin "2") (pinfunction "2_2") (pintype "passive"))
      (node (ref "C62") (pin "2") (pinfunction "2_2") (pintype "passive"))
      (node (ref "C63") (pin "1") (pinfunction "1_1") (pintype "passive"))
      (node (ref "C65") (pin "2") (pinfunction "2_2") (pintype "passive"))
      (node (ref "C66") (pin "2") (pinfunction "2_2") (pintype "passive"))
      (node (ref "C67") (pin "2") (pinfunction "2_2") (pintype "passive"))
      (node (ref "C71") (pin "1") (pinfunction "1_1") (pintype "passive"))
      (node (ref "C73") (pin "2") (pinfunction "2_2") (pintype "passive"))
      (node (ref "C75") (pin "2") (pinfunction "2_2") (pintype "passive"))
      (node (ref "C77") (pin "2") (pinfunction "2_2") (pintype "passive"))
      (node (ref "C78") (pin "2") (pinfunction "2_2") (pintype "passive"))
      (node (ref "C79") (pin "1") (pinfunction "1_1") (pintype "passive"))
      (node (ref "C81") (pin "2") (pinfunction "2_2") (pintype "passive"))
      (node (ref "C82") (pin "2") (pinfunction "2_2") (pintype "passive"))
      (node (ref "C83") (pin "2") (pinfunction "2_2") (pintype "passive"))
      (node (ref "C87") (pin "1") (pinfunction "1_1") (pintype "passive"))
      (node (ref "C89") (pin "2") (pinfunction "2_2") (pintype "passive"))
      (node (ref "C91") (pin "2") (pinfunction "2_2") (pintype "passive"))
      (node (ref "C94") (pin "1") (pinfunction "1_1") (pintype "passive"))
      (node (ref "C95") (pin "1") (pinfunction "1_1") (pintype "passive"))
      (node (ref "J3") (pin "5") (pinfunction "5_5") (pintype "passive"))
      (node (ref "J4") (pin "5") (pinfunction "5_5") (pintype "passive"))
      (node (ref "L4") (pin "2") (pinfunction "2_2") (pintype "passive"))
      (node (ref "PJ1") (pin "1") (pinfunction "1_1") (pintype "power_in"))
      (node (ref "PJ2") (pin "1") (pinfunction "1_1") (pintype "power_in"))
      (node (ref "PJ3") (pin "1") (pinfunction "1_1") (pintype "power_in"))
      (node (ref "PJ4") (pin "1") (pinfunction "1_1") (pintype "power_in"))
      (node (ref "R19") (pin "1") (pinfunction "1_1") (pintype "passive"))
      (node (ref "R32") (pin "2") (pinfunction "2_2") (pintype "passive"))
      (node (ref "R33") (pin "1") (pinfunction "1_1") (pintype "passive"))
      (node (ref "R34") (pin "1") (pinfunction "1_1") (pintype "passive"))
      (node (ref "R37") (pin "1") (pinfunction "1_1") (pintype "passive"))
      (node (ref "R50") (pin "2") (pinfunction "2_2") (pintype "passive"))
      (node (ref "R51") (pin "1") (pinfunction "1_1") (pintype "passive"))
      (node (ref "R52") (pin "1") (pinfunction "1_1") (pintype "passive"))
      (node (ref "R55") (pin "1") (pinfunction "1_1") (pintype "passive"))
      (node (ref "R68") (pin "2") (pinfunction "2_2") (pintype "passive"))
      (node (ref "R69") (pin "1") (pinfunction "1_1") (pintype "passive"))
      (node (ref "R70") (pin "1") (pinfunction "1_1") (pintype "passive"))
      (node (ref "R73") (pin "1") (pinfunction "1_1") (pintype "passive"))
      (node (ref "R86") (pin "2") (pinfunction "2_2") (pintype "passive"))
      (node (ref "R87") (pin "1") (pinfunction "1_1") (pintype "passive"))
      (node (ref "R88") (pin "1") (pinfunction "1_1") (pintype "passive"))
      (node (ref "U10") (pin "4") (pinfunction "-VS_4") (pintype "power_in"))
      (node (ref "U11") (pin "11") (pinfunction "V-_11") (pintype "passive"))
      (node (ref "U11") (pin "5") (pinfunction "+INB_5") (pintype "passive"))
      (node (ref "U12") (pin "4") (pinfunction "GND_4") (pintype "passive"))
      (node (ref "U13") (pin "4") (pinfunction "-VS_4") (pintype "power_in"))
      (node (ref "U14") (pin "11") (pinfunction "V-_11") (pintype "passive"))
      (node (ref "U14") (pin "5") (pinfunction "+INB_5") (pintype "passive"))
      (node (ref "U15") (pin "4") (pinfunction "GND_4") (pintype "passive"))
      (node (ref "U16") (pin "4") (pinfunction "-VS_4") (pintype "power_in"))
      (node (ref "U18") (pin "4") (pinfunction "GND_4") (pintype "passive"))
      (node (ref "U19") (pin "4") (pinfunction "-VS_4") (pintype "power_in"))
      (node (ref "U7") (pin "11") (pinfunction "V-_11") (pintype "passive"))
      (node (ref "U7") (pin "5") (pinfunction "+INB_5") (pintype "passive"))
      (node (ref "U8") (pin "11") (pinfunction "V-_11") (pintype "passive"))
      (node (ref "U8") (pin "5") (pinfunction "+INB_5") (pintype "passive"))
      (node (ref "U9") (pin "4") (pinfunction "GND_4") (pintype "passive"))
    )
    (net (code "15") (name "GND") (class "Default")
      (node (ref "C92") (pin "1") (pinfunction "1_1") (pintype "passive"))
      (node (ref "C93") (pin "1") (pinfunction "1_1") (pintype "passive"))
      (node (ref "L4") (pin "1") (pinfunction "1_1") (pintype "passive"))
      (node (ref "R90") (pin "1") (pinfunction "1_1") (pintype "passive"))
      (node (ref "R92") (pin "1") (pinfunction "1_1") (pintype "passive"))
      (node (ref "R94") (pin "1") (pinfunction "1_1") (pintype "passive"))
      (node (ref "R96") (pin "1") (pinfunction "1_1") (pintype "passive"))
    )
    (net (code "16") (name "Net-(C28-Pad1)") (class "Default")
      (node (ref "C28") (pin "1") (pinfunction "1_1") (pintype "passive"))
      (node (ref "R18") (pin "1") (pinfunction "1_1") (pintype "passive"))
    )
    (net (code "17") (name "Net-(C28-Pad2)") (class "Default")
      (node (ref "C28") (pin "2") (pinfunction "2_2") (pintype "passive"))
      (node (ref "R24") (pin "W") (pinfunction "W_W") (pintype "passive"))
      (node (ref "R26") (pin "1") (pinfunction "1_1") (pintype "passive"))
      (node (ref "R31") (pin "1") (pinfunction "1_1") (pintype "passive"))
    )
    (net (code "18") (name "Net-(C29-Pad1)") (class "Default")
      (node (ref "C29") (pin "1") (pinfunction "1_1") (pintype "passive"))
      (node (ref "D3") (pin "2") (pinfunction "2_2") (pintype "passive"))
      (node (ref "J7") (pin "1") (pinfunction "1_1") (pintype "passive"))
      (node (ref "R19") (pin "2") (pinfunction "2_2") (pintype "passive"))
    )
    (net (code "19") (name "Net-(C37-Pad2)") (class "Default")
      (node (ref "C37") (pin "2") (pinfunction "2_2") (pintype "passive"))
      (node (ref "R25") (pin "2") (pinfunction "2_2") (pintype "passive"))
    )
    (net (code "20") (name "Net-(C44-Pad1)") (class "Default")
      (node (ref "C44") (pin "1") (pinfunction "1_1") (pintype "passive"))
      (node (ref "R36") (pin "1") (pinfunction "1_1") (pintype "passive"))
    )
    (net (code "21") (name "Net-(C44-Pad2)") (class "Default")
      (node (ref "C44") (pin "2") (pinfunction "2_2") (pintype "passive"))
      (node (ref "R42") (pin "W") (pinfunction "W_W") (pintype "passive"))
      (node (ref "R44") (pin "1") (pinfunction "1_1") (pintype "passive"))
      (node (ref "R49") (pin "1") (pinfunction "1_1") (pintype "passive"))
    )
    (net (code "22") (name "Net-(C45-Pad1)") (class "Default")
      (node (ref "C45") (pin "1") (pinfunction "1_1") (pintype "passive"))
      (node (ref "D4") (pin "2") (pinfunction "2_2") (pintype "passive"))
      (node (ref "J8") (pin "1") (pinfunction "1_1") (pintype "passive"))
      (node (ref "R37") (pin "2") (pinfunction "2_2") (pintype "passive"))
    )
    (net (code "23") (name "Net-(C53-Pad2)") (class "Default")
      (node (ref "C53") (pin "2") (pinfunction "2_2") (pintype "passive"))
      (node (ref "R43") (pin "2") (pinfunction "2_2") (pintype "passive"))
    )
    (net (code "24") (name "Net-(C60-Pad1)") (class "Default")
      (node (ref "C60") (pin "1") (pinfunction "1_1") (pintype "passive"))
      (node (ref "R54") (pin "1") (pinfunction "1_1") (pintype "passive"))
    )
    (net (code "25") (name "Net-(C60-Pad2)") (class "Default")
      (node (ref "C60") (pin "2") (pinfunction "2_2") (pintype "passive"))
      (node (ref "R60") (pin "W") (pinfunction "W_W") (pintype "passive"))
      (node (ref "R62") (pin "1") (pinfunction "1_1") (pintype "passive"))
      (node (ref "R67") (pin "1") (pinfunction "1_1") (pintype "passive"))
    )
    (net (code "26") (name "Net-(C61-Pad1)") (class "Default")
      (node (ref "C61") (pin "1") (pinfunction "1_1") (pintype "passive"))
      (node (ref "D5") (pin "2") (pinfunction "2_2") (pintype "passive"))
      (node (ref "J9") (pin "1") (pinfunction "1_1") (pintype "passive"))
      (node (ref "R55") (pin "2") (pinfunction "2_2") (pintype "passive"))
    )
    (net (code "27") (name "Net-(C69-Pad2)") (class "Default")
      (node (ref "C69") (pin "2") (pinfunction "2_2") (pintype "passive"))
      (node (ref "R61") (pin "2") (pinfunction "2_2") (pintype "passive"))
    )
    (net (code "28") (name "Net-(C76-Pad1)") (class "Default")
      (node (ref "C76") (pin "1") (pinfunction "1_1") (pintype "passive"))
      (node (ref "R72") (pin "1") (pinfunction "1_1") (pintype "passive"))
    )
    (net (code "29") (name "Net-(C76-Pad2)") (class "Default")
      (node (ref "C76") (pin "2") (pinfunction "2_2") (pintype "passive"))
      (node (ref "R78") (pin "W") (pinfunction "W_W") (pintype "passive"))
      (node (ref "R80") (pin "1") (pinfunction "1_1") (pintype "passive"))
      (node (ref "R85") (pin "1") (pinfunction "1_1") (pintype "passive"))
    )
    (net (code "30") (name "Net-(C77-Pad1)") (class "Default")
      (node (ref "C77") (pin "1") (pinfunction "1_1") (pintype "passive"))
      (node (ref "D6") (pin "2") (pinfunction "2_2") (pintype "passive"))
      (node (ref "J10") (pin "1") (pinfunction "1_1") (pintype "passive"))
      (node (ref "R73") (pin "2") (pinfunction "2_2") (pintype "passive"))
    )
    (net (code "31") (name "Net-(C85-Pad2)") (class "Default")
      (node (ref "C85") (pin "2") (pinfunction "2_2") (pintype "passive"))
      (node (ref "R79") (pin "2") (pinfunction "2_2") (pintype "passive"))
    )
    (net (code "32") (name "Net-(PJ1-Pad2)") (class "Default")
      (node (ref "PJ1") (pin "2") (pinfunction "2_2") (pintype "power_in"))
      (node (ref "PJ1") (pin "4") (pinfunction "4_4") (pintype "power_in"))
      (node (ref "R22") (pin "1") (pinfunction "1_1") (pintype "passive"))
    )
    (net (code "33") (name "Net-(PJ1-Pad3)") (class "Default")
      (node (ref "PJ1") (pin "3") (pinfunction "3_3") (pintype "power_in"))
      (node (ref "PJ1") (pin "5") (pinfunction "5_5") (pintype "power_in"))
      (node (ref "R27") (pin "1") (pinfunction "1_1") (pintype "passive"))
    )
    (net (code "34") (name "Net-(PJ2-Pad2)") (class "Default")
      (node (ref "PJ2") (pin "2") (pinfunction "2_2") (pintype "power_in"))
      (node (ref "PJ2") (pin "4") (pinfunction "4_4") (pintype "power_in"))
      (node (ref "R40") (pin "1") (pinfunction "1_1") (pintype "passive"))
    )
    (net (code "35") (name "Net-(PJ2-Pad3)") (class "Default")
      (node (ref "PJ2") (pin "3") (pinfunction "3_3") (pintype "power_in"))
      (node (ref "PJ2") (pin "5") (pinfunction "5_5") (pintype "power_in"))
      (node (ref "R45") (pin "1") (pinfunction "1_1") (pintype "passive"))
    )
    (net (code "36") (name "Net-(PJ3-Pad2)") (class "Default")
      (node (ref "PJ3") (pin "2") (pinfunction "2_2") (pintype "power_in"))
      (node (ref "PJ3") (pin "4") (pinfunction "4_4") (pintype "power_in"))
      (node (ref "R58") (pin "1") (pinfunction "1_1") (pintype "passive"))
    )
    (net (code "37") (name "Net-(PJ3-Pad3)") (class "Default")
      (node (ref "PJ3") (pin "3") (pinfunction "3_3") (pintype "power_in"))
      (node (ref "PJ3") (pin "5") (pinfunction "5_5") (pintype "power_in"))
      (node (ref "R63") (pin "1") (pinfunction "1_1") (pintype "passive"))
    )
    (net (code "38") (name "Net-(PJ4-Pad2)") (class "Default")
      (node (ref "PJ4") (pin "2") (pinfunction "2_2") (pintype "power_in"))
      (node (ref "PJ4") (pin "4") (pinfunction "4_4") (pintype "power_in"))
      (node (ref "R76") (pin "1") (pinfunction "1_1") (pintype "passive"))
    )
    (net (code "39") (name "Net-(PJ4-Pad3)") (class "Default")
      (node (ref "PJ4") (pin "3") (pinfunction "3_3") (pintype "power_in"))
      (node (ref "PJ4") (pin "5") (pinfunction "5_5") (pintype "power_in"))
      (node (ref "R81") (pin "1") (pinfunction "1_1") (pintype "passive"))
    )
    (net (code "40") (name "Net-(U7A--INA)") (class "Default")
      (node (ref "C53") (pin "1") (pinfunction "1_1") (pintype "passive"))
      (node (ref "C56") (pin "2") (pinfunction "2_2") (pintype "passive"))
      (node (ref "R47") (pin "1") (pinfunction "1_1") (pintype "passive"))
      (node (ref "U7") (pin "2") (pinfunction "-INA_2") (pintype "passive"))
    )
    (net (code "41") (name "Net-(U7A-OUTA)") (class "Default")
      (node (ref "C56") (pin "1") (pinfunction "1_1") (pintype "passive"))
      (node (ref "R42") (pin "1") (pinfunction "1_1") (pintype "passive"))
      (node (ref "R47") (pin "2") (pinfunction "2_2") (pintype "passive"))
      (node (ref "U7") (pin "1") (pinfunction "OUTA_1") (pintype "passive"))
    )
    (net (code "42") (name "Net-(U7B--INB)") (class "Default")
      (node (ref "R36") (pin "2") (pinfunction "2_2") (pintype "passive"))
      (node (ref "R38") (pin "1") (pinfunction "1_1") (pintype "passive"))
      (node (ref "U7") (pin "6") (pinfunction "-INB_6") (pintype "passive"))
    )
    (net (code "43") (name "Net-(U7B-OUTB)") (class "Default")
      (node (ref "D4") (pin "1") (pinfunction "1_1") (pintype "passive"))
      (node (ref "R38") (pin "2") (pinfunction "2_2") (pintype "passive"))
      (node (ref "U7") (pin "7") (pinfunction "OUTB_7") (pintype "passive"))
    )
    (net (code "44") (name "Net-(U7C--INC)") (class "Default")
      (node (ref "R44") (pin "2") (pinfunction "2_2") (pintype "passive"))
      (node (ref "R46") (pin "1") (pinfunction "1_1") (pintype "passive"))
      (node (ref "U7") (pin "9") (pinfunction "-INC_9") (pintype "passive"))
    )
    (net (code "45") (name "Net-(U7C-OUTC)") (class "Default")
      (node (ref "J8") (pin "3") (pinfunction "3_3") (pintype "passive"))
      (node (ref "R46") (pin "2") (pinfunction "2_2") (pintype "passive"))
      (node (ref "U7") (pin "8") (pinfunction "OUTC_8") (pintype "passive"))
    )
    (net (code "46") (name "Net-(U7D-+IND)") (class "Default")
      (node (ref "R49") (pin "2") (pinfunction "2_2") (pintype "passive"))
      (node (ref "R51") (pin "2") (pinfunction "2_2") (pintype "passive"))
      (node (ref "U7") (pin "12") (pinfunction "+IND_12") (pintype "passive"))
    )
    (net (code "47") (name "Net-(U8A--INA)") (class "Default")
      (node (ref "C37") (pin "1") (pinfunction "1_1") (pintype "passive"))
      (node (ref "C40") (pin "2") (pinfunction "2_2") (pintype "passive"))
      (node (ref "R29") (pin "1") (pinfunction "1_1") (pintype "passive"))
      (node (ref "U8") (pin "2") (pinfunction "-INA_2") (pintype "passive"))
    )
    (net (code "48") (name "Net-(U8A-OUTA)") (class "Default")
      (node (ref "C40") (pin "1") (pinfunction "1_1") (pintype "passive"))
      (node (ref "R24") (pin "1") (pinfunction "1_1") (pintype "passive"))
      (node (ref "R29") (pin "2") (pinfunction "2_2") (pintype "passive"))
      (node (ref "U8") (pin "1") (pinfunction "OUTA_1") (pintype "passive"))
    )
    (net (code "49") (name "Net-(U8B--INB)") (class "Default")
      (node (ref "R18") (pin "2") (pinfunction "2_2") (pintype "passive"))
      (node (ref "R20") (pin "1") (pinfunction "1_1") (pintype "passive"))
      (node (ref "U8") (pin "6") (pinfunction "-INB_6") (pintype "passive"))
    )
    (net (code "50") (name "Net-(U8B-OUTB)") (class "Default")
      (node (ref "D3") (pin "1") (pinfunction "1_1") (pintype "passive"))
      (node (ref "R20") (pin "2") (pinfunction "2_2") (pintype "passive"))
      (node (ref "U8") (pin "7") (pinfunction "OUTB_7") (pintype "passive"))
    )
    (net (code "51") (name "Net-(U8C--INC)") (class "Default")
      (node (ref "R26") (pin "2") (pinfunction "2_2") (pintype "passive"))
      (node (ref "R28") (pin "1") (pinfunction "1_1") (pintype "passive"))
      (node (ref "U8") (pin "9") (pinfunction "-INC_9") (pintype "passive"))
    )
    (net (code "52") (name "Net-(U8C-OUTC)") (class "Default")
      (node (ref "J7") (pin "3") (pinfunction "3_3") (pintype "passive"))
      (node (ref "R28") (pin "2") (pinfunction "2_2") (pintype "passive"))
      (node (ref "U8") (pin "8") (pinfunction "OUTC_8") (pintype "passive"))
    )
    (net (code "53") (name "Net-(U8D-+IND)") (class "Default")
      (node (ref "R31") (pin "2") (pinfunction "2_2") (pintype "passive"))
      (node (ref "R33") (pin "2") (pinfunction "2_2") (pintype "passive"))
      (node (ref "U8") (pin "12") (pinfunction "+IND_12") (pintype "passive"))
    )
    (net (code "54") (name "Net-(U9A-+INA)") (class "Default")
      (node (ref "C41") (pin "1") (pinfunction "1_1") (pintype "passive"))
      (node (ref "R30") (pin "2") (pinfunction "2_2") (pintype "passive"))
      (node (ref "R32") (pin "1") (pinfunction "1_1") (pintype "passive"))
      (node (ref "U9") (pin "3") (pinfunction "+INA_3") (pintype "passive"))
    )
    (net (code "55") (name "Net-(U9B-+INB)") (class "Default")
      (node (ref "J7") (pin "2") (pinfunction "2_2") (pintype "passive"))
      (node (ref "U9") (pin "5") (pinfunction "+INB_5") (pintype "passive"))
    )
    (net (code "56") (name "Net-(U9B--INB)") (class "Default")
      (node (ref "R89") (pin "1") (pinfunction "1_1") (pintype "passive"))
      (node (ref "U9") (pin "6") (pinfunction "-INB_6") (pintype "passive"))
      (node (ref "U9") (pin "7") (pinfunction "OUTB_7") (pintype "passive"))
    )
    (net (code "57") (name "Net-(U10-+IN)") (class "Default")
      (node (ref "C36") (pin "1") (pinfunction "1_1") (pintype "passive"))
      (node (ref "C38") (pin "2") (pinfunction "2_2") (pintype "passive"))
      (node (ref "R27") (pin "2") (pinfunction "2_2") (pintype "passive"))
      (node (ref "U10") (pin "3") (pinfunction "+IN_3") (pintype "passive"))
    )
    (net (code "58") (name "Net-(U10-+RG)") (class "Default")
      (node (ref "R21") (pin "2") (pinfunction "2_2") (pintype "passive"))
      (node (ref "U10") (pin "8") (pinfunction "+RG_8") (pintype "power_in"))
    )
    (net (code "59") (name "Net-(U10--IN)") (class "Default")
      (node (ref "C32") (pin "1") (pinfunction "1_1") (pintype "passive"))
      (node (ref "C36") (pin "2") (pinfunction "2_2") (pintype "passive"))
      (node (ref "R22") (pin "2") (pinfunction "2_2") (pintype "passive"))
      (node (ref "U10") (pin "2") (pinfunction "-IN_2") (pintype "passive"))
    )
    (net (code "60") (name "Net-(U10--RG)") (class "Default")
      (node (ref "R21") (pin "1") (pinfunction "1_1") (pintype "passive"))
      (node (ref "U10") (pin "1") (pinfunction "-RG_1") (pintype "passive"))
    )
    (net (code "61") (name "Net-(U10-OUT)") (class "Default")
      (node (ref "R25") (pin "1") (pinfunction "1_1") (pintype "passive"))
      (node (ref "U10") (pin "6") (pinfunction "OUT_6") (pintype "passive"))
    )
    (net (code "62") (name "Net-(U11A--INA)") (class "Default")
      (node (ref "C69") (pin "1") (pinfunction "1_1") (pintype "passive"))
      (node (ref "C72") (pin "2") (pinfunction "2_2") (pintype "passive"))
      (node (ref "R65") (pin "1") (pinfunction "1_1") (pintype "passive"))
      (node (ref "U11") (pin "2") (pinfunction "-INA_2") (pintype "passive"))
    )
    (net (code "63") (name "Net-(U11A-OUTA)") (class "Default")
      (node (ref "C72") (pin "1") (pinfunction "1_1") (pintype "passive"))
      (node (ref "R60") (pin "1") (pinfunction "1_1") (pintype "passive"))
      (node (ref "R65") (pin "2") (pinfunction "2_2") (pintype "passive"))
      (node (ref "U11") (pin "1") (pinfunction "OUTA_1") (pintype "passive"))
    )
    (net (code "64") (name "Net-(U11B--INB)") (class "Default")
      (node (ref "R54") (pin "2") (pinfunction "2_2") (pintype "passive"))
      (node (ref "R56") (pin "1") (pinfunction "1_1") (pintype "passive"))
      (node (ref "U11") (pin "6") (pinfunction "-INB_6") (pintype "passive"))
    )
    (net (code "65") (name "Net-(U11B-OUTB)") (class "Default")
      (node (ref "D5") (pin "1") (pinfunction "1_1") (pintype "passive"))
      (node (ref "R56") (pin "2") (pinfunction "2_2") (pintype "passive"))
      (node (ref "U11") (pin "7") (pinfunction "OUTB_7") (pintype "passive"))
    )
    (net (code "66") (name "Net-(U11C--INC)") (class "Default")
      (node (ref "R62") (pin "2") (pinfunction "2_2") (pintype "passive"))
      (node (ref "R64") (pin "1") (pinfunction "1_1") (pintype "passive"))
      (node (ref "U11") (pin "9") (pinfunction "-INC_9") (pintype "passive"))
    )
    (net (code "67") (name "Net-(U11C-OUTC)") (class "Default")
      (node (ref "J9") (pin "3") (pinfunction "3_3") (pintype "passive"))
      (node (ref "R64") (pin "2") (pinfunction "2_2") (pintype "passive"))
      (node (ref "U11") (pin "8") (pinfunction "OUTC_8") (pintype "passive"))
    )
    (net (code "68") (name "Net-(U11D-+IND)") (class "Default")
      (node (ref "R67") (pin "2") (pinfunction "2_2") (pintype "passive"))
      (node (ref "R69") (pin "2") (pinfunction "2_2") (pintype "passive"))
      (node (ref "U11") (pin "12") (pinfunction "+IND_12") (pintype "passive"))
    )
    (net (code "69") (name "Net-(U12A-+INA)") (class "Default")
      (node (ref "C57") (pin "1") (pinfunction "1_1") (pintype "passive"))
      (node (ref "R48") (pin "2") (pinfunction "2_2") (pintype "passive"))
      (node (ref "R50") (pin "1") (pinfunction "1_1") (pintype "passive"))
      (node (ref "U12") (pin "3") (pinfunction "+INA_3") (pintype "passive"))
    )
    (net (code "70") (name "Net-(U12B-+INB)") (class "Default")
      (node (ref "J8") (pin "2") (pinfunction "2_2") (pintype "passive"))
      (node (ref "U12") (pin "5") (pinfunction "+INB_5") (pintype "passive"))
    )
    (net (code "71") (name "Net-(U12B--INB)") (class "Default")
      (node (ref "R91") (pin "1") (pinfunction "1_1") (pintype "passive"))
      (node (ref "U12") (pin "6") (pinfunction "-INB_6") (pintype "passive"))
      (node (ref "U12") (pin "7") (pinfunction "OUTB_7") (pintype "passive"))
    )
    (net (code "72") (name "Net-(U13-+IN)") (class "Default")
      (node (ref "C52") (pin "1") (pinfunction "1_1") (pintype "passive"))
      (node (ref "C54") (pin "2") (pinfunction "2_2") (pintype "passive"))
      (node (ref "R45") (pin "2") (pinfunction "2_2") (pintype "passive"))
      (node (ref "U13") (pin "3") (pinfunction "+IN_3") (pintype "passive"))
    )
    (net (code "73") (name "Net-(U13-+RG)") (class "Default")
      (node (ref "R39") (pin "2") (pinfunction "2_2") (pintype "passive"))
      (node (ref "U13") (pin "8") (pinfunction "+RG_8") (pintype "power_in"))
    )
    (net (code "74") (name "Net-(U13--IN)") (class "Default")
      (node (ref "C48") (pin "1") (pinfunction "1_1") (pintype "passive"))
      (node (ref "C52") (pin "2") (pinfunction "2_2") (pintype "passive"))
      (node (ref "R40") (pin "2") (pinfunction "2_2") (pintype "passive"))
      (node (ref "U13") (pin "2") (pinfunction "-IN_2") (pintype "passive"))
    )
    (net (code "75") (name "Net-(U13--RG)") (class "Default")
      (node (ref "R39") (pin "1") (pinfunction "1_1") (pintype "passive"))
      (node (ref "U13") (pin "1") (pinfunction "-RG_1") (pintype "passive"))
    )
    (net (code "76") (name "Net-(U13-OUT)") (class "Default")
      (node (ref "R43") (pin "1") (pinfunction "1_1") (pintype "passive"))
      (node (ref "U13") (pin "6") (pinfunction "OUT_6") (pintype "passive"))
    )
    (net (code "77") (name "Net-(U14A--INA)") (class "Default")
      (node (ref "C85") (pin "1") (pinfunction "1_1") (pintype "passive"))
      (node (ref "C88") (pin "2") (pinfunction "2_2") (pintype "passive"))
      (node (ref "R83") (pin "1") (pinfunction "1_1") (pintype "passive"))
      (node (ref "U14") (pin "2") (pinfunction "-INA_2") (pintype "passive"))
    )
    (net (code "78") (name "Net-(U14A-OUTA)") (class "Default")
      (node (ref "C88") (pin "1") (pinfunction "1_1") (pintype "passive"))
      (node (ref "R78") (pin "1") (pinfunction "1_1") (pintype "passive"))
      (node (ref "R83") (pin "2") (pinfunction "2_2") (pintype "passive"))
      (node (ref "U14") (pin "1") (pinfunction "OUTA_1") (pintype "passive"))
    )
    (net (code "79") (name "Net-(U14B--INB)") (class "Default")
      (node (ref "R72") (pin "2") (pinfunction "2_2") (pintype "passive"))
      (node (ref "R74") (pin "1") (pinfunction "1_1") (pintype "passive"))
      (node (ref "U14") (pin "6") (pinfunction "-INB_6") (pintype "passive"))
    )
    (net (code "80") (name "Net-(U14B-OUTB)") (class "Default")
      (node (ref "D6") (pin "1") (pinfunction "1_1") (pintype "passive"))
      (node (ref "R74") (pin "2") (pinfunction "2_2") (pintype "passive"))
      (node (ref "U14") (pin "7") (pinfunction "OUTB_7") (pintype "passive"))
    )
    (net (code "81") (name "Net-(U14C--INC)") (class "Default")
      (node (ref "R80") (pin "2") (pinfunction "2_2") (pintype "passive"))
      (node (ref "R82") (pin "1") (pinfunction "1_1") (pintype "passive"))
      (node (ref "U14") (pin "9") (pinfunction "-INC_9") (pintype "passive"))
    )
    (net (code "82") (name "Net-(U14C-OUTC)") (class "Default")
      (node (ref "J10") (pin "3") (pinfunction "3_3") (pintype "passive"))
      (node (ref "R82") (pin "2") (pinfunction "2_2") (pintype "passive"))
      (node (ref "U14") (pin "8") (pinfunction "OUTC_8") (pintype "passive"))
    )
    (net (code "83") (name "Net-(U14D-+IND)") (class "Default")
      (node (ref "R85") (pin "2") (pinfunction "2_2") (pintype "passive"))
      (node (ref "R87") (pin "2") (pinfunction "2_2") (pintype "passive"))
      (node (ref "U14") (pin "12") (pinfunction "+IND_12") (pintype "passive"))
    )
    (net (code "84") (name "Net-(U15A-+INA)") (class "Default")
      (node (ref "C73") (pin "1") (pinfunction "1_1") (pintype "passive"))
      (node (ref "R66") (pin "2") (pinfunction "2_2") (pintype "passive"))
      (node (ref "R68") (pin "1") (pinfunction "1_1") (pintype "passive"))
      (node (ref "U15") (pin "3") (pinfunction "+INA_3") (pintype "passive"))
    )
    (net (code "85") (name "Net-(U15B-+INB)") (class "Default")
      (node (ref "J9") (pin "2") (pinfunction "2_2") (pintype "passive"))
      (node (ref "U15") (pin "5") (pinfunction "+INB_5") (pintype "passive"))
    )
    (net (code "86") (name "Net-(U15B--INB)") (class "Default")
      (node (ref "R93") (pin "1") (pinfunction "1_1") (pintype "passive"))
      (node (ref "U15") (pin "6") (pinfunction "-INB_6") (pintype "passive"))
      (node (ref "U15") (pin "7") (pinfunction "OUTB_7") (pintype "passive"))
    )
    (net (code "87") (name "Net-(U16-+IN)") (class "Default")
      (node (ref "C68") (pin "1") (pinfunction "1_1") (pintype "passive"))
      (node (ref "C70") (pin "2") (pinfunction "2_2") (pintype "passive"))
      (node (ref "R63") (pin "2") (pinfunction "2_2") (pintype "passive"))
      (node (ref "U16") (pin "3") (pinfunction "+IN_3") (pintype "passive"))
    )
    (net (code "88") (name "Net-(U16-+RG)") (class "Default")
      (node (ref "R57") (pin "2") (pinfunction "2_2") (pintype "passive"))
      (node (ref "U16") (pin "8") (pinfunction "+RG_8") (pintype "power_in"))
    )
    (net (code "89") (name "Net-(U16--IN)") (class "Default")
      (node (ref "C64") (pin "1") (pinfunction "1_1") (pintype "passive"))
      (node (ref "C68") (pin "2") (pinfunction "2_2") (pintype "passive"))
      (node (ref "R58") (pin "2") (pinfunction "2_2") (pintype "passive"))
      (node (ref "U16") (pin "2") (pinfunction "-IN_2") (pintype "passive"))
    )
    (net (code "90") (name "Net-(U16--RG)") (class "Default")
      (node (ref "R57") (pin "1") (pinfunction "1_1") (pintype "passive"))
      (node (ref "U16") (pin "1") (pinfunction "-RG_1") (pintype "passive"))
    )
    (net (code "91") (name "Net-(U16-OUT)") (class "Default")
      (node (ref "R61") (pin "1") (pinfunction "1_1") (pintype "passive"))
      (node (ref "U16") (pin "6") (pinfunction "OUT_6") (pintype "passive"))
    )
    (net (code "92") (name "Net-(U18A-+INA)") (class "Default")
      (node (ref "C89") (pin "1") (pinfunction "1_1") (pintype "passive"))
      (node (ref "R84") (pin "2") (pinfunction "2_2") (pintype "passive"))
      (node (ref "R86") (pin "1") (pinfunction "1_1") (pintype "passive"))
      (node (ref "U18") (pin "3") (pinfunction "+INA_3") (pintype "passive"))
    )
    (net (code "93") (name "Net-(U18B-+INB)") (class "Default")
      (node (ref "J10") (pin "2") (pinfunction "2_2") (pintype "passive"))
      (node (ref "U18") (pin "5") (pinfunction "+INB_5") (pintype "passive"))
    )
    (net (code "94") (name "Net-(U18B--INB)") (class "Default")
      (node (ref "R95") (pin "1") (pinfunction "1_1") (pintype "passive"))
      (node (ref "U18") (pin "6") (pinfunction "-INB_6") (pintype "passive"))
      (node (ref "U18") (pin "7") (pinfunction "OUTB_7") (pintype "passive"))
    )
    (net (code "95") (name "Net-(U19-+IN)") (class "Default")
      (node (ref "C84") (pin "1") (pinfunction "1_1") (pintype "passive"))
      (node (ref "C86") (pin "2") (pinfunction "2_2") (pintype "passive"))
      (node (ref "R81") (pin "2") (pinfunction "2_2") (pintype "passive"))
      (node (ref "U19") (pin "3") (pinfunction "+IN_3") (pintype "passive"))
    )
    (net (code "96") (name "Net-(U19-+RG)") (class "Default")
      (node (ref "R75") (pin "2") (pinfunction "2_2") (pintype "passive"))
      (node (ref "U19") (pin "8") (pinfunction "+RG_8") (pintype "power_in"))
    )
    (net (code "97") (name "Net-(U19--IN)") (class "Default")
      (node (ref "C80") (pin "1") (pinfunction "1_1") (pintype "passive"))
      (node (ref "C84") (pin "2") (pinfunction "2_2") (pintype "passive"))
      (node (ref "R76") (pin "2") (pinfunction "2_2") (pintype "passive"))
      (node (ref "U19") (pin "2") (pinfunction "-IN_2") (pintype "passive"))
    )
    (net (code "98") (name "Net-(U19--RG)") (class "Default")
      (node (ref "R75") (pin "1") (pinfunction "1_1") (pintype "passive"))
      (node (ref "U19") (pin "1") (pinfunction "-RG_1") (pintype "passive"))
    )
    (net (code "99") (name "Net-(U19-OUT)") (class "Default")
      (node (ref "R79") (pin "1") (pinfunction "1_1") (pintype "passive"))
      (node (ref "U19") (pin "6") (pinfunction "OUT_6") (pintype "passive"))
    )
    (net (code "100") (name "VCC") (class "Default")
      (node (ref "C30") (pin "1") (pinfunction "1_1") (pintype "passive"))
      (node (ref "C31") (pin "2") (pinfunction "2_2") (pintype "passive"))
      (node (ref "C34") (pin "1") (pinfunction "1_1") (pintype "passive"))
      (node (ref "C35") (pin "1") (pinfunction "1_1") (pintype "passive"))
      (node (ref "C46") (pin "1") (pinfunction "1_1") (pintype "passive"))
      (node (ref "C47") (pin "2") (pinfunction "2_2") (pintype "passive"))
      (node (ref "C50") (pin "1") (pinfunction "1_1") (pintype "passive"))
      (node (ref "C51") (pin "1") (pinfunction "1_1") (pintype "passive"))
      (node (ref "C62") (pin "1") (pinfunction "1_1") (pintype "passive"))
      (node (ref "C63") (pin "2") (pinfunction "2_2") (pintype "passive"))
      (node (ref "C66") (pin "1") (pinfunction "1_1") (pintype "passive"))
      (node (ref "C67") (pin "1") (pinfunction "1_1") (pintype "passive"))
      (node (ref "C78") (pin "1") (pinfunction "1_1") (pintype "passive"))
      (node (ref "C79") (pin "2") (pinfunction "2_2") (pintype "passive"))
      (node (ref "C82") (pin "1") (pinfunction "1_1") (pintype "passive"))
      (node (ref "C83") (pin "1") (pinfunction "1_1") (pintype "passive"))
      (node (ref "C94") (pin "2") (pinfunction "2_2") (pintype "passive"))
      (node (ref "C95") (pin "2") (pinfunction "2_2") (pintype "passive"))
      (node (ref "L3") (pin "2") (pinfunction "2_2") (pintype "passive"))
      (node (ref "R30") (pin "1") (pinfunction "1_1") (pintype "passive"))
      (node (ref "R48") (pin "1") (pinfunction "1_1") (pintype "passive"))
      (node (ref "R66") (pin "1") (pinfunction "1_1") (pintype "passive"))
      (node (ref "R84") (pin "1") (pinfunction "1_1") (pintype "passive"))
      (node (ref "U10") (pin "7") (pinfunction "+VS_7") (pintype "passive"))
      (node (ref "U11") (pin "4") (pinfunction "V+_4") (pintype "passive"))
      (node (ref "U12") (pin "8") (pinfunction "VCC_8") (pintype "passive"))
      (node (ref "U13") (pin "7") (pinfunction "+VS_7") (pintype "passive"))
      (node (ref "U14") (pin "4") (pinfunction "V+_4") (pintype "passive"))
      (node (ref "U15") (pin "8") (pinfunction "VCC_8") (pintype "passive"))
      (node (ref "U16") (pin "7") (pinfunction "+VS_7") (pintype "passive"))
      (node (ref "U18") (pin "8") (pinfunction "VCC_8") (pintype "passive"))
      (node (ref "U19") (pin "7") (pinfunction "+VS_7") (pintype "passive"))
      (node (ref "U7") (pin "4") (pinfunction "V+_4") (pintype "passive"))
      (node (ref "U8") (pin "4") (pinfunction "V+_4") (pintype "passive"))
      (node (ref "U9") (pin "8") (pinfunction "VCC_8") (pintype "passive"))
    )
    (net (code "101") (name "VCC{slash}2CH1") (class "Default")
      (node (ref "C32") (pin "2") (pinfunction "2_2") (pintype "passive"))
      (node (ref "C33") (pin "1") (pinfunction "1_1") (pintype "passive"))
      (node (ref "C38") (pin "1") (pinfunction "1_1") (pintype "passive"))
      (node (ref "C39") (pin "2") (pinfunction "2_2") (pintype "passive"))
      (node (ref "C43") (pin "1") (pinfunction "1_1") (pintype "passive"))
      (node (ref "R24") (pin "2") (pinfunction "2_2") (pintype "passive"))
      (node (ref "U10") (pin "5") (pinfunction "REF_5") (pintype "passive"))
      (node (ref "U8") (pin "10") (pinfunction "+INC_10") (pintype "passive"))
      (node (ref "U8") (pin "3") (pinfunction "+INA_3") (pintype "passive"))
      (node (ref "U9") (pin "1") (pinfunction "OUTA_1") (pintype "passive"))
      (node (ref "U9") (pin "2") (pinfunction "-INA_2") (pintype "passive"))
    )
    (net (code "102") (name "VCC{slash}2CH2") (class "Default")
      (node (ref "C48") (pin "2") (pinfunction "2_2") (pintype "passive"))
      (node (ref "C49") (pin "1") (pinfunction "1_1") (pintype "passive"))
      (node (ref "C54") (pin "1") (pinfunction "1_1") (pintype "passive"))
      (node (ref "C55") (pin "2") (pinfunction "2_2") (pintype "passive"))
      (node (ref "C59") (pin "1") (pinfunction "1_1") (pintype "passive"))
      (node (ref "R42") (pin "2") (pinfunction "2_2") (pintype "passive"))
      (node (ref "U12") (pin "1") (pinfunction "OUTA_1") (pintype "passive"))
      (node (ref "U12") (pin "2") (pinfunction "-INA_2") (pintype "passive"))
      (node (ref "U13") (pin "5") (pinfunction "REF_5") (pintype "passive"))
      (node (ref "U7") (pin "10") (pinfunction "+INC_10") (pintype "passive"))
      (node (ref "U7") (pin "3") (pinfunction "+INA_3") (pintype "passive"))
    )
    (net (code "103") (name "VCC{slash}2CH3") (class "Default")
      (node (ref "C64") (pin "2") (pinfunction "2_2") (pintype "passive"))
      (node (ref "C65") (pin "1") (pinfunction "1_1") (pintype "passive"))
      (node (ref "C70") (pin "1") (pinfunction "1_1") (pintype "passive"))
      (node (ref "C71") (pin "2") (pinfunction "2_2") (pintype "passive"))
      (node (ref "C75") (pin "1") (pinfunction "1_1") (pintype "passive"))
      (node (ref "R60") (pin "2") (pinfunction "2_2") (pintype "passive"))
      (node (ref "U11") (pin "10") (pinfunction "+INC_10") (pintype "passive"))
      (node (ref "U11") (pin "3") (pinfunction "+INA_3") (pintype "passive"))
      (node (ref "U15") (pin "1") (pinfunction "OUTA_1") (pintype "passive"))
      (node (ref "U15") (pin "2") (pinfunction "-INA_2") (pintype "passive"))
      (node (ref "U16") (pin "5") (pinfunction "REF_5") (pintype "passive"))
    )
    (net (code "104") (name "VCC{slash}2CH4") (class "Default")
      (node (ref "C80") (pin "2") (pinfunction "2_2") (pintype "passive"))
      (node (ref "C81") (pin "1") (pinfunction "1_1") (pintype "passive"))
      (node (ref "C86") (pin "1") (pinfunction "1_1") (pintype "passive"))
      (node (ref "C87") (pin "2") (pinfunction "2_2") (pintype "passive"))
      (node (ref "C91") (pin "1") (pinfunction "1_1") (pintype "passive"))
      (node (ref "R78") (pin "2") (pinfunction "2_2") (pintype "passive"))
      (node (ref "U14") (pin "10") (pinfunction "+INC_10") (pintype "passive"))
      (node (ref "U14") (pin "3") (pinfunction "+INA_3") (pintype "passive"))
      (node (ref "U18") (pin "1") (pinfunction "OUTA_1") (pintype "passive"))
      (node (ref "U18") (pin "2") (pinfunction "-INA_2") (pintype "passive"))
      (node (ref "U19") (pin "5") (pinfunction "REF_5") (pintype "passive"))
    )
  )
)
